# beltpack_v1.net
KiCad netlist of a schematic drawn in EAGLE
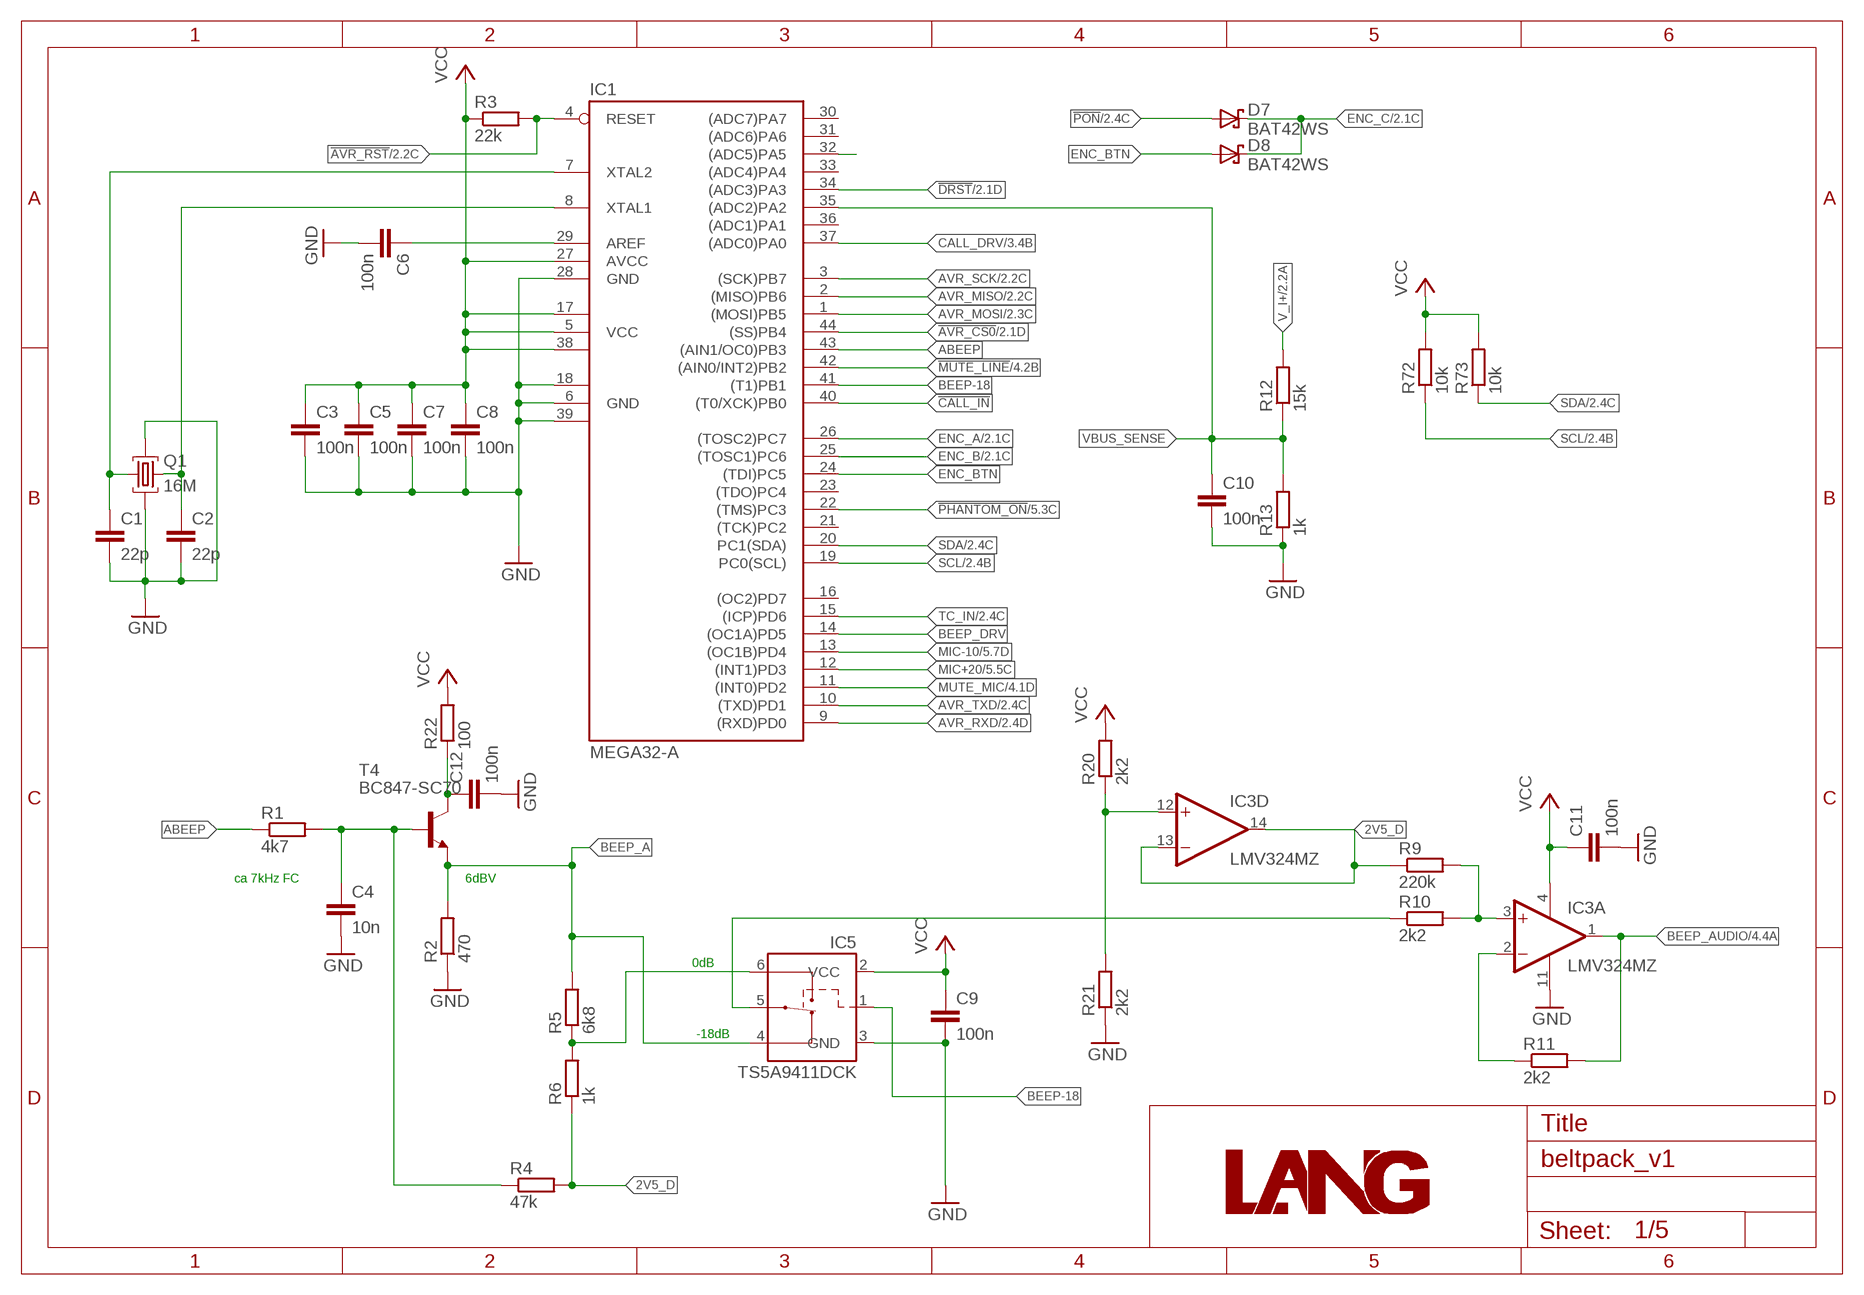
[diagram p0: schematic, sheet 1]
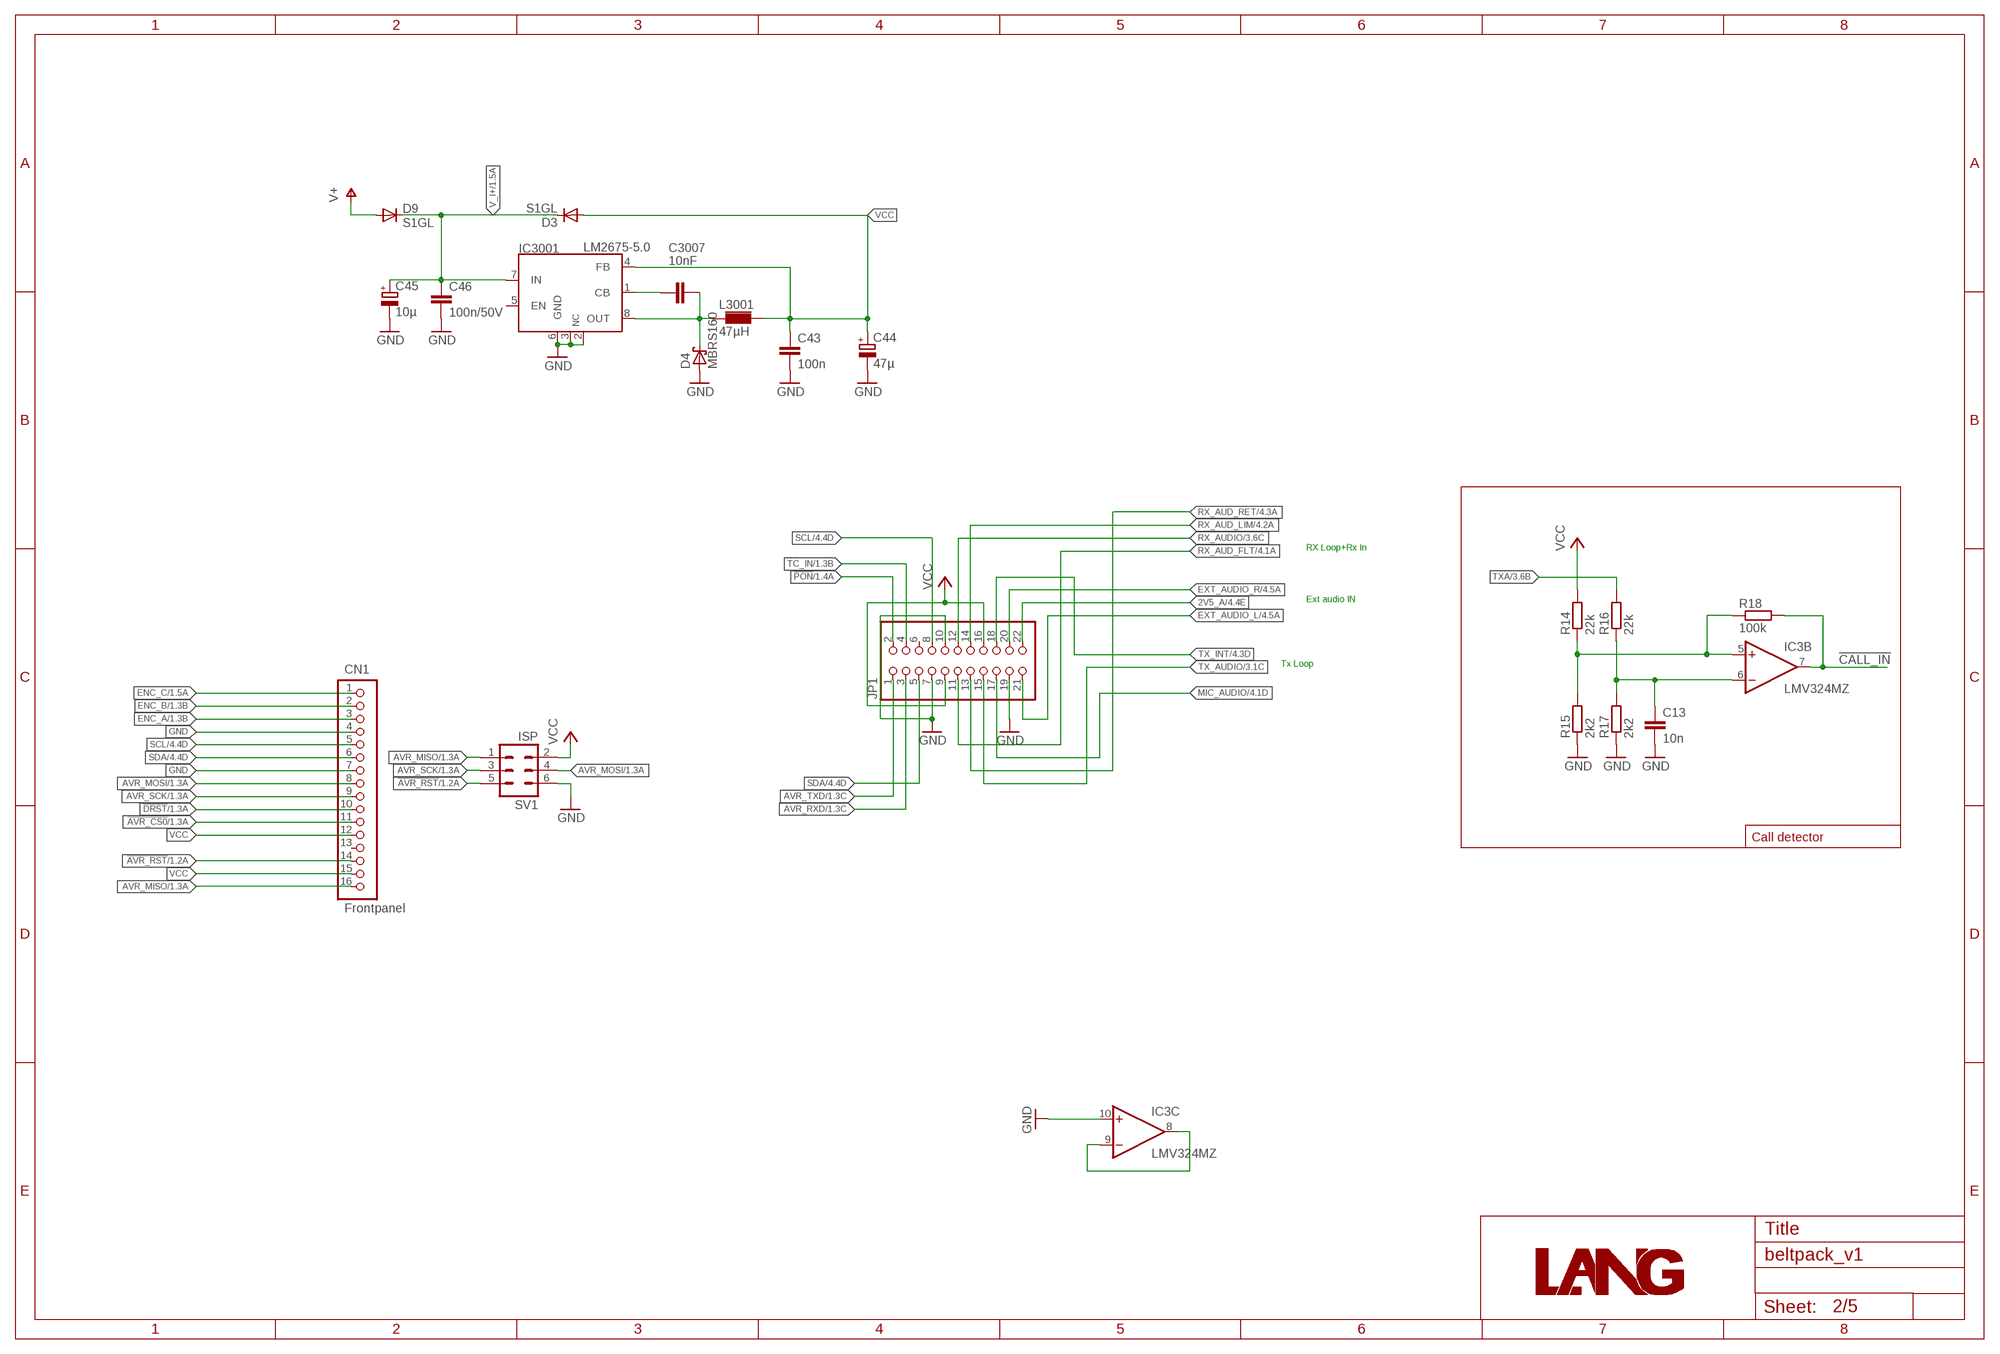
[diagram p1: schematic, sheet 2]
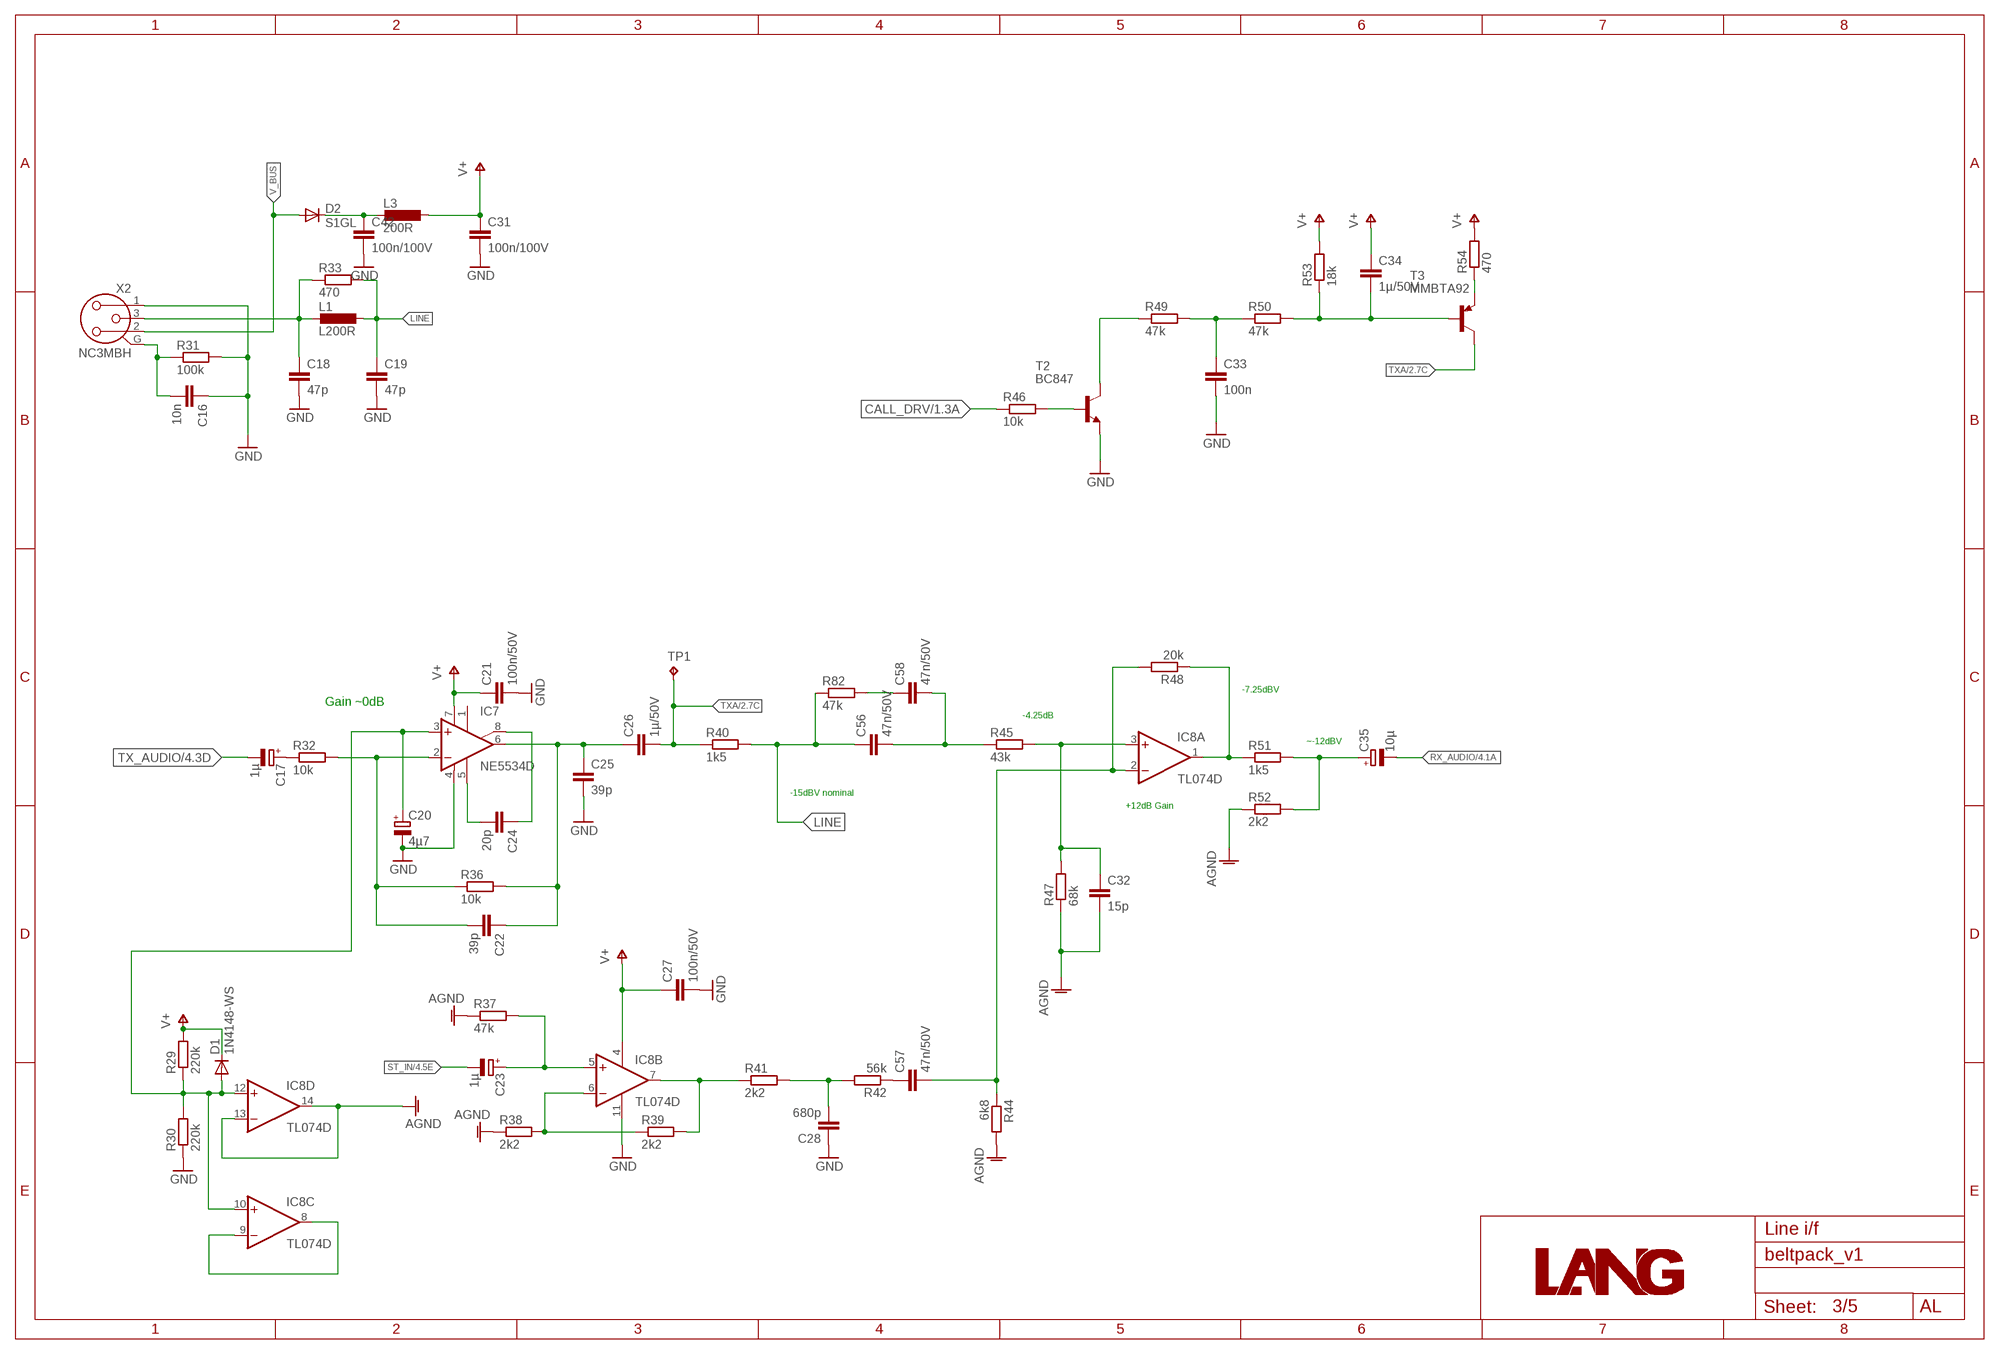
[diagram p2: schematic, sheet 3]
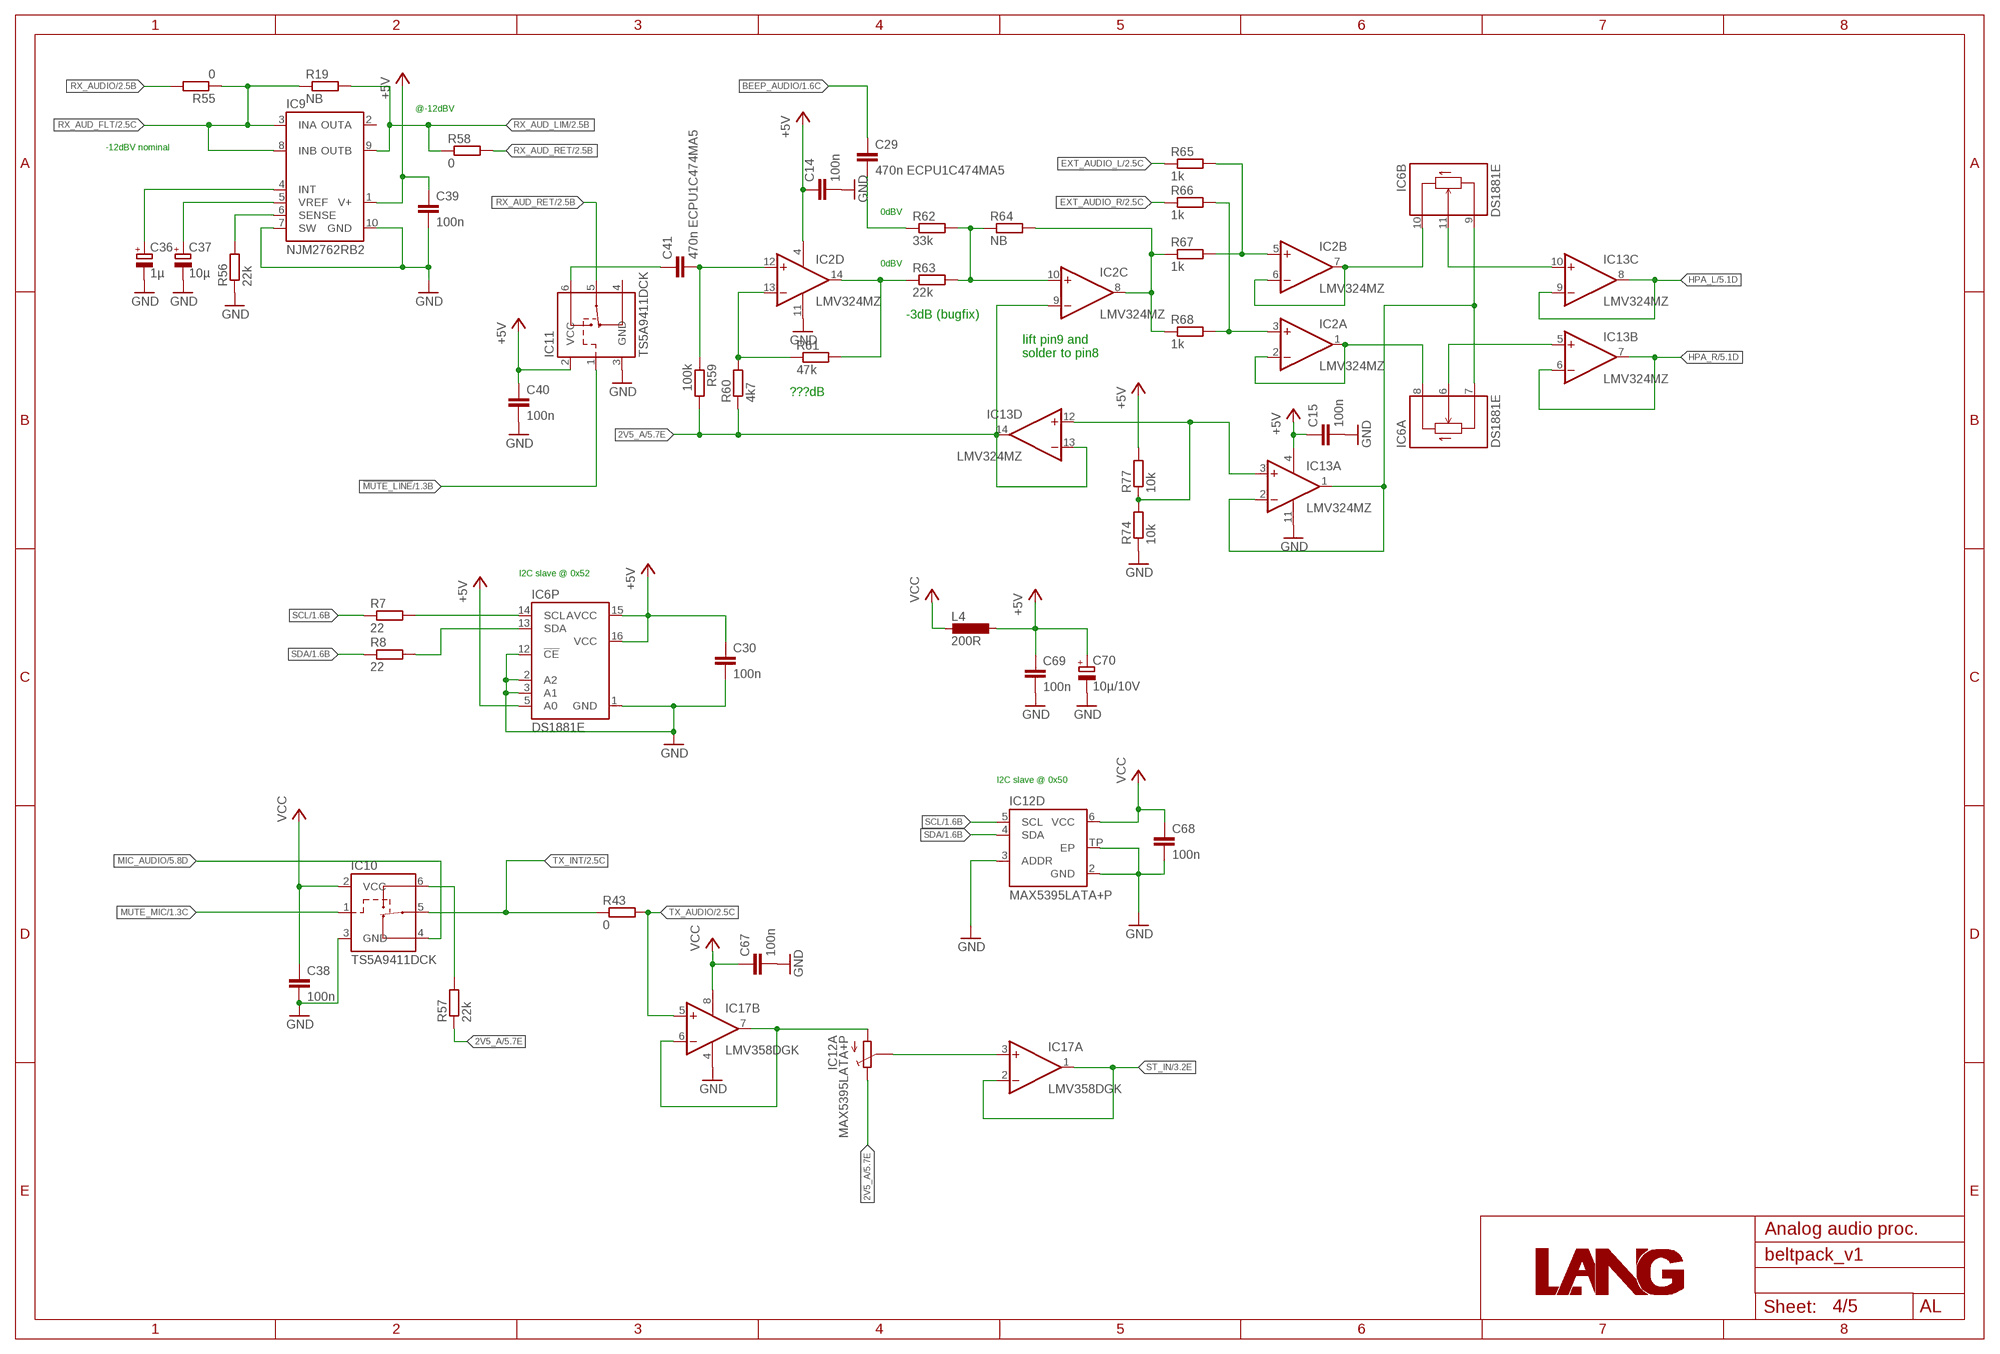
[diagram p3: schematic, sheet 4]
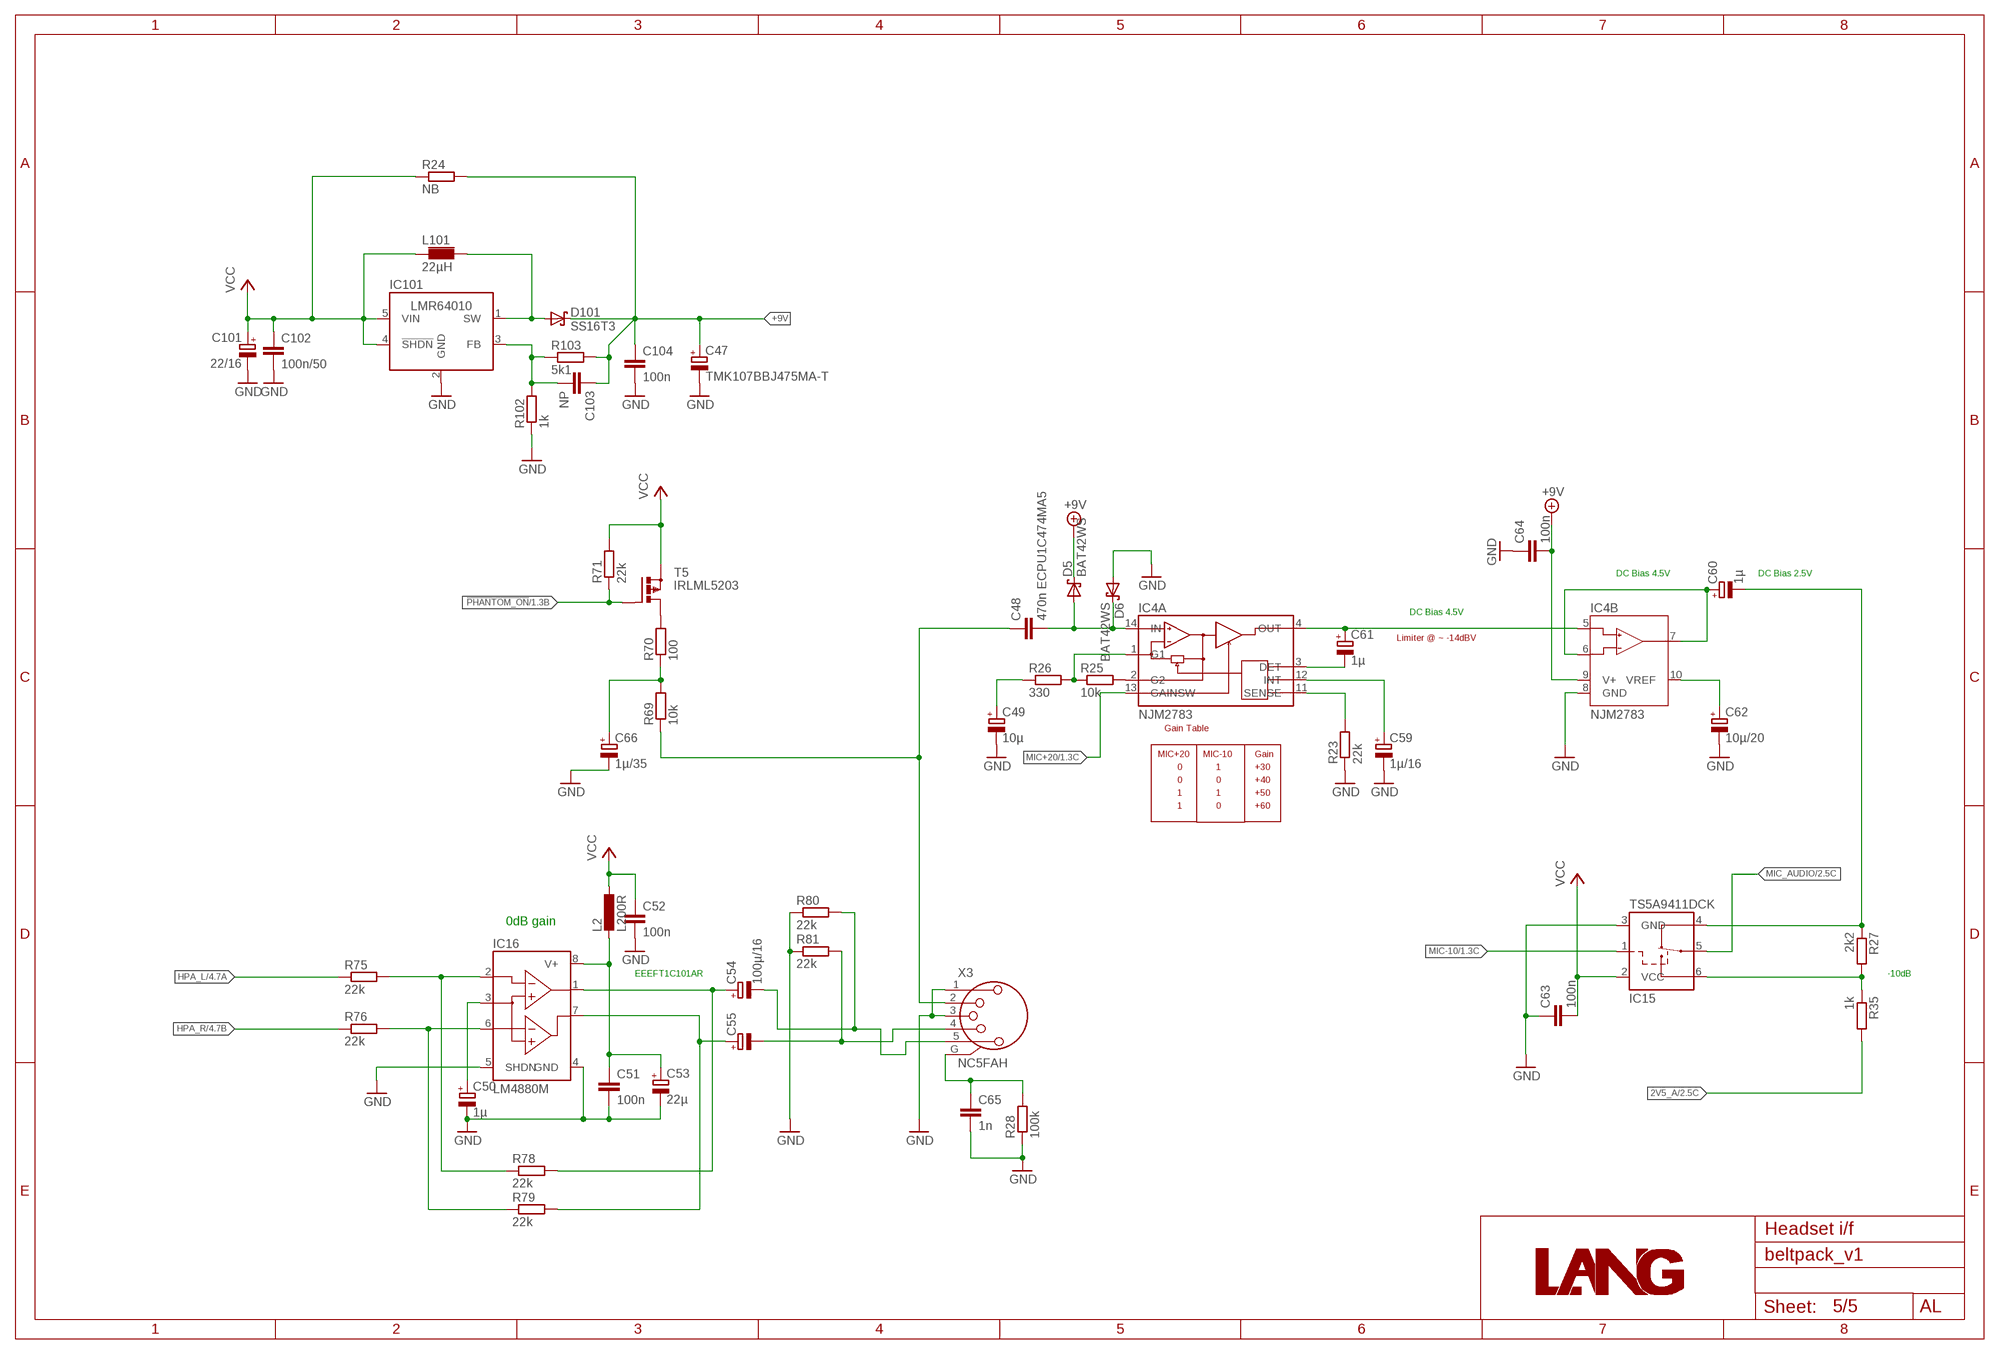
[diagram p4: schematic, sheet 5]

(export (version "E")
  (design (tool "Eeschema 10.0.6"))
  (components
    (comp (ref "C13")
      (value "10n")
      (footprint "eagle-import:C0603")
      (libsource (lib "eagle-import") (part "C-EUC0603"))
    )
    (comp (ref "C43")
      (value "100n")
      (footprint "eagle-import:C0603")
      (libsource (lib "eagle-import") (part "C-EUC0603"))
    )
    (comp (ref "C44")
      (value "47µ")
      (footprint "eagle-import:PANASONIC_B")
      (libsource (lib "eagle-import") (part "CPOL-EUB"))
    )
    (comp (ref "C45")
      (value "10µ")
      (footprint "eagle-import:PANASONIC_C")
      (libsource (lib "eagle-import") (part "CPOL-EUC"))
    )
    (comp (ref "C46")
      (value "100n/50V")
      (footprint "eagle-import:C0805")
      (libsource (lib "eagle-import") (part "C-EUC0805"))
    )
    (comp (ref "C3007")
      (value "10nF")
      (footprint "eagle-import:C0805")
      (libsource (lib "eagle-import") (part "C-EUC0805"))
    )
    (comp (ref "CN1")
      (value "Frontpanel")
      (footprint "eagle-import:MOLEX-505278-1633")
      (libsource (lib "eagle-import") (part "MOLEX-505278-1633"))
    )
    (comp (ref "D3")
      (value "S1GL")
      (footprint "eagle-import:DO219AB")
      (libsource (lib "eagle-import") (part "DIODE-DO219AB"))
    )
    (comp (ref "D4")
      (value "MBRS160")
      (footprint "eagle-import:SMB")
      (libsource (lib "eagle-import") (part "SCHOTTKY-DIODESMD"))
    )
    (comp (ref "D9")
      (value "S1GL")
      (footprint "eagle-import:DO219AB")
      (libsource (lib "eagle-import") (part "DIODE-DO219AB"))
    )
    (comp (ref "IC3")
      (value "LMV324MZ")
      (footprint "eagle-import:TSSOP14")
      (libsource (lib "eagle-import") (part "LMV324?MZ"))
    )
    (comp (ref "IC3001")
      (value "LM2675-5.0")
      (footprint "eagle-import:SO-08")
      (libsource (lib "eagle-import") (part "LM2676_SOIC"))
    )
    (comp (ref "JP1")
      (value "PINHD-2X11")
      (footprint "eagle-import:2X11")
      (libsource (lib "eagle-import") (part "PINHD-2X11"))
    )
    (comp (ref "L3001")
      (value "47µH")
      (footprint "eagle-import:PISM")
      (libsource (lib "eagle-import") (part "L-PISM"))
    )
    (comp (ref "R14")
      (value "22k")
      (footprint "eagle-import:R0603")
      (libsource (lib "eagle-import") (part "R-EU_R0603"))
    )
    (comp (ref "R15")
      (value "2k2")
      (footprint "eagle-import:R0603")
      (libsource (lib "eagle-import") (part "R-EU_R0603"))
    )
    (comp (ref "R16")
      (value "22k")
      (footprint "eagle-import:R0603")
      (libsource (lib "eagle-import") (part "R-EU_R0603"))
    )
    (comp (ref "R17")
      (value "2k2")
      (footprint "eagle-import:R0603")
      (libsource (lib "eagle-import") (part "R-EU_R0603"))
    )
    (comp (ref "R18")
      (value "100k")
      (footprint "eagle-import:R0603")
      (libsource (lib "eagle-import") (part "R-EU_R0603"))
    )
    (comp (ref "SV1")
      (value "ISP")
      (footprint "eagle-import:ML6")
      (libsource (lib "eagle-import") (part "ML6"))
    )
    (comp (ref "C1")
      (value "22p")
      (footprint "eagle-import:C0603")
      (libsource (lib "eagle-import") (part "C-EUC0603"))
    )
    (comp (ref "C2")
      (value "22p")
      (footprint "eagle-import:C0603")
      (libsource (lib "eagle-import") (part "C-EUC0603"))
    )
    (comp (ref "C3")
      (value "100n")
      (footprint "eagle-import:C0603")
      (libsource (lib "eagle-import") (part "C-EUC0603"))
    )
    (comp (ref "C4")
      (value "10n")
      (footprint "eagle-import:C0603")
      (libsource (lib "eagle-import") (part "C-EUC0603"))
    )
    (comp (ref "C5")
      (value "100n")
      (footprint "eagle-import:C0603")
      (libsource (lib "eagle-import") (part "C-EUC0603"))
    )
    (comp (ref "C6")
      (value "100n")
      (footprint "eagle-import:C0603")
      (libsource (lib "eagle-import") (part "C-EUC0603"))
    )
    (comp (ref "C7")
      (value "100n")
      (footprint "eagle-import:C0603")
      (libsource (lib "eagle-import") (part "C-EUC0603"))
    )
    (comp (ref "C8")
      (value "100n")
      (footprint "eagle-import:C0603")
      (libsource (lib "eagle-import") (part "C-EUC0603"))
    )
    (comp (ref "C9")
      (value "100n")
      (footprint "eagle-import:C0603")
      (libsource (lib "eagle-import") (part "C-EUC0603"))
    )
    (comp (ref "C10")
      (value "100n")
      (footprint "eagle-import:C0603")
      (libsource (lib "eagle-import") (part "C-EUC0603"))
    )
    (comp (ref "C11")
      (value "100n")
      (footprint "eagle-import:C0603")
      (libsource (lib "eagle-import") (part "C-EUC0603"))
    )
    (comp (ref "C12")
      (value "100n")
      (footprint "eagle-import:C0603")
      (libsource (lib "eagle-import") (part "C-EUC0603"))
    )
    (comp (ref "D7")
      (value "BAT42WS")
      (footprint "eagle-import:SOD323R_INFINEON")
      (libsource (lib "eagle-import") (part "BAT4WS2"))
    )
    (comp (ref "D8")
      (value "BAT42WS")
      (footprint "eagle-import:SOD323R_INFINEON")
      (libsource (lib "eagle-import") (part "BAT4WS2"))
    )
    (comp (ref "IC1")
      (value "MEGA32-A")
      (footprint "eagle-import:TQFP44")
      (libsource (lib "eagle-import") (part "MEGA32-A"))
    )
    (comp (ref "IC5")
      (value "TS5A9411DCK")
      (footprint "eagle-import:SC70-6L")
      (libsource (lib "eagle-import") (part "TS5A9411DCK"))
    )
    (comp (ref "Q1")
      (value "16M")
      (footprint "eagle-import:MT")
      (libsource (lib "eagle-import") (part "CRYSTAL_SHIELDEDMT"))
    )
    (comp (ref "R1")
      (value "4k7")
      (footprint "eagle-import:R0603")
      (libsource (lib "eagle-import") (part "R-EU_R0603"))
    )
    (comp (ref "R2")
      (value "470")
      (footprint "eagle-import:R0603")
      (libsource (lib "eagle-import") (part "R-EU_R0603"))
    )
    (comp (ref "R3")
      (value "22k")
      (footprint "eagle-import:R0603")
      (libsource (lib "eagle-import") (part "R-EU_R0603"))
    )
    (comp (ref "R4")
      (value "47k")
      (footprint "eagle-import:R0603")
      (libsource (lib "eagle-import") (part "R-EU_R0603"))
    )
    (comp (ref "R5")
      (value "6k8")
      (footprint "eagle-import:R0603")
      (libsource (lib "eagle-import") (part "R-EU_R0603"))
    )
    (comp (ref "R6")
      (value "1k")
      (footprint "eagle-import:R0603")
      (libsource (lib "eagle-import") (part "R-EU_R0603"))
    )
    (comp (ref "R9")
      (value "220k")
      (footprint "eagle-import:R0603")
      (libsource (lib "eagle-import") (part "R-EU_R0603"))
    )
    (comp (ref "R10")
      (value "2k2")
      (footprint "eagle-import:R0603")
      (libsource (lib "eagle-import") (part "R-EU_R0603"))
    )
    (comp (ref "R11")
      (value "2k2")
      (footprint "eagle-import:R0603")
      (libsource (lib "eagle-import") (part "R-EU_R0603"))
    )
    (comp (ref "R12")
      (value "15k")
      (footprint "eagle-import:R0603")
      (libsource (lib "eagle-import") (part "R-EU_R0603"))
    )
    (comp (ref "R13")
      (value "1k")
      (footprint "eagle-import:R0603")
      (libsource (lib "eagle-import") (part "R-EU_R0603"))
    )
    (comp (ref "R20")
      (value "2k2")
      (footprint "eagle-import:R0603")
      (libsource (lib "eagle-import") (part "R-EU_R0603"))
    )
    (comp (ref "R21")
      (value "2k2")
      (footprint "eagle-import:R0603")
      (libsource (lib "eagle-import") (part "R-EU_R0603"))
    )
    (comp (ref "R22")
      (value "100")
      (footprint "eagle-import:R0603")
      (libsource (lib "eagle-import") (part "R-EU_R0603"))
    )
    (comp (ref "R72")
      (value "10k")
      (footprint "eagle-import:R0603")
      (libsource (lib "eagle-import") (part "R-EU_R0603"))
    )
    (comp (ref "R73")
      (value "10k")
      (footprint "eagle-import:R0603")
      (libsource (lib "eagle-import") (part "R-EU_R0603"))
    )
    (comp (ref "T4")
      (value "BC847-SC70")
      (footprint "eagle-import:SC70")
      (libsource (lib "eagle-import") (part "BC847-SC70"))
    )
    (comp (ref "C16")
      (value "10n")
      (footprint "eagle-import:C0805")
      (libsource (lib "eagle-import") (part "C-EUC0805"))
    )
    (comp (ref "C17")
      (value "1µ")
      (footprint "eagle-import:PANASONIC_B")
      (libsource (lib "eagle-import") (part "CPOL-EUB"))
    )
    (comp (ref "C18")
      (value "47p")
      (footprint "eagle-import:C0603")
      (libsource (lib "eagle-import") (part "C-EUC0603"))
    )
    (comp (ref "C19")
      (value "47p")
      (footprint "eagle-import:C0603")
      (libsource (lib "eagle-import") (part "C-EUC0603"))
    )
    (comp (ref "C20")
      (value "4µ7")
      (footprint "eagle-import:PANASONIC_B")
      (libsource (lib "eagle-import") (part "CPOL-EUB"))
    )
    (comp (ref "C21")
      (value "100n/50V")
      (footprint "eagle-import:C0805")
      (libsource (lib "eagle-import") (part "C-EUC0805"))
    )
    (comp (ref "C22")
      (value "39p")
      (footprint "eagle-import:C0603")
      (libsource (lib "eagle-import") (part "C-EUC0603"))
    )
    (comp (ref "C23")
      (value "1µ")
      (footprint "eagle-import:PANASONIC_B")
      (libsource (lib "eagle-import") (part "CPOL-EUB"))
    )
    (comp (ref "C24")
      (value "20p")
      (footprint "eagle-import:C0603")
      (libsource (lib "eagle-import") (part "C-EUC0603"))
    )
    (comp (ref "C25")
      (value "39p")
      (footprint "eagle-import:C0603")
      (libsource (lib "eagle-import") (part "C-EUC0603"))
    )
    (comp (ref "C26")
      (value "1µ/50V")
      (footprint "eagle-import:C1206")
      (libsource (lib "eagle-import") (part "C-EUC1206"))
    )
    (comp (ref "C27")
      (value "100n/50V")
      (footprint "eagle-import:C0805")
      (libsource (lib "eagle-import") (part "C-EUC0805"))
    )
    (comp (ref "C28")
      (value "680p")
      (footprint "eagle-import:C0603")
      (libsource (lib "eagle-import") (part "C-EUC0603"))
    )
    (comp (ref "C31")
      (value "100n/100V")
      (footprint "eagle-import:C1206")
      (libsource (lib "eagle-import") (part "C-EUC1206"))
    )
    (comp (ref "C32")
      (value "15p")
      (footprint "eagle-import:C0603")
      (libsource (lib "eagle-import") (part "C-EUC0603"))
    )
    (comp (ref "C33")
      (value "100n")
      (footprint "eagle-import:C0603")
      (libsource (lib "eagle-import") (part "C-EUC0603"))
    )
    (comp (ref "C34")
      (value "1µ/50V")
      (footprint "eagle-import:C1206")
      (libsource (lib "eagle-import") (part "C-EUC1206"))
    )
    (comp (ref "C35")
      (value "10µ")
      (footprint "eagle-import:PANASONIC_B")
      (libsource (lib "eagle-import") (part "CPOL-EUB"))
    )
    (comp (ref "C42")
      (value "100n/100V")
      (footprint "eagle-import:C1206")
      (libsource (lib "eagle-import") (part "C-EUC1206"))
    )
    (comp (ref "C56")
      (value "47n/50V")
      (footprint "eagle-import:C_PAN_ECHU_E1")
      (libsource (lib "eagle-import") (part "C-EUPAN_E1"))
    )
    (comp (ref "C57")
      (value "47n/50V")
      (footprint "eagle-import:C_PAN_ECHU_E1")
      (libsource (lib "eagle-import") (part "C-EUPAN_E1"))
    )
    (comp (ref "C58")
      (value "47n/50V")
      (footprint "eagle-import:C_PAN_ECHU_E1")
      (libsource (lib "eagle-import") (part "C-EUPAN_E1"))
    )
    (comp (ref "D1")
      (value "1N4148-WS")
      (footprint "eagle-import:SOD323")
      (libsource (lib "eagle-import") (part "1N4148-WS"))
    )
    (comp (ref "D2")
      (value "S1GL")
      (footprint "eagle-import:DO219AB")
      (libsource (lib "eagle-import") (part "DIODE-DO219AB"))
    )
    (comp (ref "IC7")
      (value "NE5534D")
      (footprint "eagle-import:SO08")
      (libsource (lib "eagle-import") (part "NE5534D"))
    )
    (comp (ref "IC8")
      (value "TL074D")
      (footprint "eagle-import:SO14")
      (libsource (lib "eagle-import") (part "TL074D"))
    )
    (comp (ref "L1")
      (value "L200R")
      (footprint "eagle-import:R0805")
      (libsource (lib "eagle-import") (part "L-EU_L0805"))
    )
    (comp (ref "L3")
      (value "200R")
      (footprint "eagle-import:R0805")
      (libsource (lib "eagle-import") (part "L-EU_L0805"))
    )
    (comp (ref "R29")
      (value "220k")
      (footprint "eagle-import:R0603")
      (libsource (lib "eagle-import") (part "R-EU_R0603"))
    )
    (comp (ref "R30")
      (value "220k")
      (footprint "eagle-import:R0603")
      (libsource (lib "eagle-import") (part "R-EU_R0603"))
    )
    (comp (ref "R31")
      (value "100k")
      (footprint "eagle-import:R0805")
      (libsource (lib "eagle-import") (part "R-EU_R0805"))
    )
    (comp (ref "R32")
      (value "10k")
      (footprint "eagle-import:R0603")
      (libsource (lib "eagle-import") (part "R-EU_R0603"))
    )
    (comp (ref "R33")
      (value "470")
      (footprint "eagle-import:R0603")
      (libsource (lib "eagle-import") (part "R-EU_R0603"))
    )
    (comp (ref "R36")
      (value "10k")
      (footprint "eagle-import:R0603")
      (libsource (lib "eagle-import") (part "R-EU_R0603"))
    )
    (comp (ref "R37")
      (value "47k")
      (footprint "eagle-import:R0603")
      (libsource (lib "eagle-import") (part "R-EU_R0603"))
    )
    (comp (ref "R38")
      (value "2k2")
      (footprint "eagle-import:R0603")
      (libsource (lib "eagle-import") (part "R-EU_R0603"))
    )
    (comp (ref "R39")
      (value "2k2")
      (footprint "eagle-import:R0603")
      (libsource (lib "eagle-import") (part "R-EU_R0603"))
    )
    (comp (ref "R40")
      (value "1k5")
      (footprint "eagle-import:R1206")
      (libsource (lib "eagle-import") (part "R-EU_R1206"))
    )
    (comp (ref "R41")
      (value "2k2")
      (footprint "eagle-import:R0603")
      (libsource (lib "eagle-import") (part "R-EU_R0603"))
    )
    (comp (ref "R42")
      (value "56k")
      (footprint "eagle-import:R0603")
      (libsource (lib "eagle-import") (part "R-EU_R0603"))
    )
    (comp (ref "R44")
      (value "6k8")
      (footprint "eagle-import:R0603")
      (libsource (lib "eagle-import") (part "R-EU_R0603"))
    )
    (comp (ref "R45")
      (value "43k")
      (footprint "eagle-import:R0603")
      (libsource (lib "eagle-import") (part "R-EU_R0603"))
    )
    (comp (ref "R46")
      (value "10k")
      (footprint "eagle-import:R0603")
      (libsource (lib "eagle-import") (part "R-EU_R0603"))
    )
    (comp (ref "R47")
      (value "68k")
      (footprint "eagle-import:R0603")
      (libsource (lib "eagle-import") (part "R-EU_R0603"))
    )
    (comp (ref "R48")
      (value "20k")
      (footprint "eagle-import:R0603")
      (libsource (lib "eagle-import") (part "R-EU_R0603"))
    )
    (comp (ref "R49")
      (value "47k")
      (footprint "eagle-import:R0603")
      (libsource (lib "eagle-import") (part "R-EU_R0603"))
    )
    (comp (ref "R50")
      (value "47k")
      (footprint "eagle-import:R0603")
      (libsource (lib "eagle-import") (part "R-EU_R0603"))
    )
    (comp (ref "R51")
      (value "1k5")
      (footprint "eagle-import:R0603")
      (libsource (lib "eagle-import") (part "R-EU_R0603"))
    )
    (comp (ref "R52")
      (value "2k2")
      (footprint "eagle-import:R0603")
      (libsource (lib "eagle-import") (part "R-EU_R0603"))
    )
    (comp (ref "R53")
      (value "18k")
      (footprint "eagle-import:R0603")
      (libsource (lib "eagle-import") (part "R-EU_R0603"))
    )
    (comp (ref "R54")
      (value "470")
      (footprint "eagle-import:R0805")
      (libsource (lib "eagle-import") (part "R-EU_R0805"))
    )
    (comp (ref "R82")
      (value "47k")
      (footprint "eagle-import:R0603")
      (libsource (lib "eagle-import") (part "R-EU_R0603"))
    )
    (comp (ref "T2")
      (value "BC847")
      (footprint "eagle-import:SOT23")
      (libsource (lib "eagle-import") (part "BC847"))
    )
    (comp (ref "T3")
      (value "MMBTA92")
      (footprint "eagle-import:SOT23")
      (libsource (lib "eagle-import") (part "MMBTA92"))
    )
    (comp (ref "TP1")
      (value "XA")
      (footprint "eagle-import:B1,27")
      (libsource (lib "eagle-import") (part "TPB1,27"))
    )
    (comp (ref "X2")
      (value "NC3MBH")
      (footprint "eagle-import:NC3MBH")
      (libsource (lib "eagle-import") (part "NC3MBH"))
    )
    (comp (ref "C47")
      (value "TMK107BBJ475MA-T")
      (footprint "eagle-import:PANASONIC_B")
      (libsource (lib "eagle-import") (part "CPOL-EUB"))
    )
    (comp (ref "C48")
      (value "470n ECPU1C474MA5")
      (footprint "eagle-import:C_PANASONIC_H3")
      (libsource (lib "eagle-import") (part "C-EUPAN_H3"))
    )
    (comp (ref "C49")
      (value "10µ")
      (footprint "eagle-import:PANASONIC_B")
      (libsource (lib "eagle-import") (part "CPOL-EUB"))
    )
    (comp (ref "C50")
      (value "1µ")
      (footprint "eagle-import:PANASONIC_B")
      (libsource (lib "eagle-import") (part "CPOL-EUB"))
    )
    (comp (ref "C51")
      (value "100n")
      (footprint "eagle-import:C0603")
      (libsource (lib "eagle-import") (part "C-EUC0603"))
    )
    (comp (ref "C52")
      (value "100n")
      (footprint "eagle-import:C0603")
      (libsource (lib "eagle-import") (part "C-EUC0603"))
    )
    (comp (ref "C53")
      (value "22µ")
      (footprint "eagle-import:PANASONIC_C")
      (libsource (lib "eagle-import") (part "CPOL-EUC"))
    )
    (comp (ref "C54")
      (value "100µ/16")
      (footprint "eagle-import:PANASONIC_C")
      (libsource (lib "eagle-import") (part "CPOL-EUC"))
    )
    (comp (ref "C55")
      (value "100µ/16")
      (footprint "eagle-import:PANASONIC_C")
      (libsource (lib "eagle-import") (part "CPOL-EUC"))
    )
    (comp (ref "C59")
      (value "1µ/16")
      (footprint "eagle-import:A_3216-18R")
      (libsource (lib "eagle-import") (part "CPOL-EUA/3216-18R"))
    )
    (comp (ref "C60")
      (value "1µ")
      (footprint "eagle-import:PANASONIC_B")
      (libsource (lib "eagle-import") (part "CPOL-EUB"))
    )
    (comp (ref "C61")
      (value "1µ")
      (footprint "eagle-import:PANASONIC_B")
      (libsource (lib "eagle-import") (part "CPOL-EUB"))
    )
    (comp (ref "C62")
      (value "10µ/20")
      (footprint "eagle-import:B_3528-21R")
      (libsource (lib "eagle-import") (part "CPOL-EUB/3528-21R"))
    )
    (comp (ref "C63")
      (value "100n")
      (footprint "eagle-import:C0402")
      (libsource (lib "eagle-import") (part "C-EUC0402"))
    )
    (comp (ref "C64")
      (value "100n")
      (footprint "eagle-import:C0603")
      (libsource (lib "eagle-import") (part "C-EUC0603"))
    )
    (comp (ref "C65")
      (value "1n")
      (footprint "eagle-import:C0603")
      (libsource (lib "eagle-import") (part "C-EUC0603"))
    )
    (comp (ref "C66")
      (value "1µ/35")
      (footprint "eagle-import:B_3528-21R")
      (libsource (lib "eagle-import") (part "CPOL-EUB/3528-21R"))
    )
    (comp (ref "C101")
      (value "22/16")
      (footprint "eagle-import:B_3528-21R")
      (libsource (lib "eagle-import") (part "CPOL-EUB/3528-21R"))
    )
    (comp (ref "C102")
      (value "100n/50")
      (footprint "eagle-import:C0805")
      (libsource (lib "eagle-import") (part "C-EUC0805"))
    )
    (comp (ref "C103")
      (value "NP")
      (footprint "eagle-import:C0603")
      (libsource (lib "eagle-import") (part "C-EUC0603"))
    )
    (comp (ref "C104")
      (value "100n")
      (footprint "eagle-import:C0603")
      (libsource (lib "eagle-import") (part "C-EUC0603"))
    )
    (comp (ref "D5")
      (value "BAT42WS")
      (footprint "eagle-import:SOD323R_INFINEON")
      (libsource (lib "eagle-import") (part "BAT4WS2"))
    )
    (comp (ref "D6")
      (value "BAT42WS")
      (footprint "eagle-import:SOD323R_INFINEON")
      (libsource (lib "eagle-import") (part "BAT4WS2"))
    )
    (comp (ref "D101")
      (value "SS16T3")
      (footprint "eagle-import:SMA")
      (libsource (lib "eagle-import") (part "SS16T3"))
    )
    (comp (ref "IC4")
      (value "NJM2783")
      (footprint "eagle-import:TSSOP14")
      (libsource (lib "eagle-import") (part "NJM2783"))
    )
    (comp (ref "IC15")
      (value "TS5A9411DCK")
      (footprint "eagle-import:SC70-6L")
      (libsource (lib "eagle-import") (part "TS5A9411DCK"))
    )
    (comp (ref "IC16")
      (value "LM4880M")
      (footprint "eagle-import:SOIC8")
      (libsource (lib "eagle-import") (part "LM4880M"))
    )
    (comp (ref "IC101")
      (value "LMR64010")
      (footprint "eagle-import:SOT23-5")
      (libsource (lib "eagle-import") (part "LMR64010"))
    )
    (comp (ref "L2")
      (value "L200R")
      (footprint "eagle-import:R0805")
      (libsource (lib "eagle-import") (part "L-EU_L0805"))
    )
    (comp (ref "L101")
      (value "22µH")
      (footprint "eagle-import:PISG")
      (libsource (lib "eagle-import") (part "L-PISG"))
    )
    (comp (ref "R23")
      (value "22k")
      (footprint "eagle-import:R0603")
      (libsource (lib "eagle-import") (part "R-EU_R0603"))
    )
    (comp (ref "R24")
      (value "NB")
      (footprint "eagle-import:R0603")
      (libsource (lib "eagle-import") (part "R-EU_R0603"))
    )
    (comp (ref "R25")
      (value "10k")
      (footprint "eagle-import:R0603")
      (libsource (lib "eagle-import") (part "R-EU_R0603"))
    )
    (comp (ref "R26")
      (value "330")
      (footprint "eagle-import:R0603")
      (libsource (lib "eagle-import") (part "R-EU_R0603"))
    )
    (comp (ref "R27")
      (value "2k2")
      (footprint "eagle-import:R0603")
      (libsource (lib "eagle-import") (part "R-EU_R0603"))
    )
    (comp (ref "R28")
      (value "100k")
      (footprint "eagle-import:R0603")
      (libsource (lib "eagle-import") (part "R-EU_R0603"))
    )
    (comp (ref "R35")
      (value "1k")
      (footprint "eagle-import:R0603")
      (libsource (lib "eagle-import") (part "R-EU_R0603"))
    )
    (comp (ref "R69")
      (value "10k")
      (footprint "eagle-import:R0603")
      (libsource (lib "eagle-import") (part "R-EU_R0603"))
    )
    (comp (ref "R70")
      (value "100")
      (footprint "eagle-import:R0603")
      (libsource (lib "eagle-import") (part "R-EU_R0603"))
    )
    (comp (ref "R71")
      (value "22k")
      (footprint "eagle-import:R0603")
      (libsource (lib "eagle-import") (part "R-EU_R0603"))
    )
    (comp (ref "R75")
      (value "22k")
      (footprint "eagle-import:R0603")
      (libsource (lib "eagle-import") (part "R-EU_R0603"))
    )
    (comp (ref "R76")
      (value "22k")
      (footprint "eagle-import:R0603")
      (libsource (lib "eagle-import") (part "R-EU_R0603"))
    )
    (comp (ref "R78")
      (value "22k")
      (footprint "eagle-import:R0603")
      (libsource (lib "eagle-import") (part "R-EU_R0603"))
    )
    (comp (ref "R79")
      (value "22k")
      (footprint "eagle-import:R0603")
      (libsource (lib "eagle-import") (part "R-EU_R0603"))
    )
    (comp (ref "R80")
      (value "22k")
      (footprint "eagle-import:R0603")
      (libsource (lib "eagle-import") (part "R-EU_R0603"))
    )
    (comp (ref "R81")
      (value "22k")
      (footprint "eagle-import:R0603")
      (libsource (lib "eagle-import") (part "R-EU_R0603"))
    )
    (comp (ref "R102")
      (value "1k")
      (footprint "eagle-import:R0603")
      (libsource (lib "eagle-import") (part "R-EU_R0603"))
    )
    (comp (ref "R103")
      (value "5k1")
      (footprint "eagle-import:R0603")
      (libsource (lib "eagle-import") (part "R-EU_R0603"))
    )
    (comp (ref "T5")
      (value "IRLML5203")
      (footprint "eagle-import:SOT23")
      (libsource (lib "eagle-import") (part "IRLML5203"))
    )
    (comp (ref "X3")
      (value "NC5FAH")
      (footprint "eagle-import:NC5FAH")
      (libsource (lib "eagle-import") (part "NC5FAH"))
    )
    (comp (ref "C14")
      (value "100n")
      (footprint "eagle-import:C0603")
      (libsource (lib "eagle-import") (part "C-EUC0603"))
    )
    (comp (ref "C15")
      (value "100n")
      (footprint "eagle-import:C0603")
      (libsource (lib "eagle-import") (part "C-EUC0603"))
    )
    (comp (ref "C29")
      (value "470n ECPU1C474MA5")
      (footprint "eagle-import:C_PANASONIC_H3")
      (libsource (lib "eagle-import") (part "C-EUPAN_H3"))
    )
    (comp (ref "C30")
      (value "100n")
      (footprint "eagle-import:C0603")
      (libsource (lib "eagle-import") (part "C-EUC0603"))
    )
    (comp (ref "C36")
      (value "1µ")
      (footprint "eagle-import:PANASONIC_B")
      (libsource (lib "eagle-import") (part "CPOL-EUB"))
    )
    (comp (ref "C37")
      (value "10µ")
      (footprint "eagle-import:PANASONIC_B")
      (libsource (lib "eagle-import") (part "CPOL-EUB"))
    )
    (comp (ref "C38")
      (value "100n")
      (footprint "eagle-import:C0402")
      (libsource (lib "eagle-import") (part "C-EUC0402"))
    )
    (comp (ref "C39")
      (value "100n")
      (footprint "eagle-import:C0603")
      (libsource (lib "eagle-import") (part "C-EUC0603"))
    )
    (comp (ref "C40")
      (value "100n")
      (footprint "eagle-import:C0603")
      (libsource (lib "eagle-import") (part "C-EUC0603"))
    )
    (comp (ref "C41")
      (value "470n ECPU1C474MA5")
      (footprint "eagle-import:C_PANASONIC_H3")
      (libsource (lib "eagle-import") (part "C-EUPAN_H3"))
    )
    (comp (ref "C67")
      (value "100n")
      (footprint "eagle-import:C0603")
      (libsource (lib "eagle-import") (part "C-EUC0603"))
    )
    (comp (ref "C68")
      (value "100n")
      (footprint "eagle-import:C0603")
      (libsource (lib "eagle-import") (part "C-EUC0603"))
    )
    (comp (ref "C69")
      (value "100n")
      (footprint "eagle-import:C0603")
      (libsource (lib "eagle-import") (part "C-EUC0603"))
    )
    (comp (ref "C70")
      (value "10µ/10V")
      (footprint "eagle-import:A_3216-18R")
      (libsource (lib "eagle-import") (part "CPOL-EUA/3216-18R"))
    )
    (comp (ref "IC2")
      (value "LMV324MZ")
      (footprint "eagle-import:TSSOP14")
      (libsource (lib "eagle-import") (part "LMV324?MZ"))
    )
    (comp (ref "IC6")
      (value "DS1881E")
      (footprint "eagle-import:TSSOP16")
      (libsource (lib "eagle-import") (part "DS1881E"))
    )
    (comp (ref "IC9")
      (value "NJM2762RB2")
      (footprint "eagle-import:MSOP10")
      (libsource (lib "eagle-import") (part "NJM2762RB2"))
    )
    (comp (ref "IC10")
      (value "TS5A9411DCK")
      (footprint "eagle-import:SC70-6L")
      (libsource (lib "eagle-import") (part "TS5A9411DCK"))
    )
    (comp (ref "IC11")
      (value "TS5A9411DCK")
      (footprint "eagle-import:SC70-6L")
      (libsource (lib "eagle-import") (part "TS5A9411DCK"))
    )
    (comp (ref "IC12")
      (value "MAX5395LATA+P")
      (footprint "eagle-import:8TDFN-EP")
      (libsource (lib "eagle-import") (part "MAX5395ATA+PL"))
    )
    (comp (ref "IC13")
      (value "LMV324MZ")
      (footprint "eagle-import:TSSOP14")
      (libsource (lib "eagle-import") (part "LMV324?MZ"))
    )
    (comp (ref "IC17")
      (value "LMV358DGK")
      (footprint "eagle-import:VSOP8")
      (libsource (lib "eagle-import") (part "LMV358?DGK"))
    )
    (comp (ref "L4")
      (value "200R")
      (footprint "eagle-import:R0805")
      (libsource (lib "eagle-import") (part "L-EU_L0805"))
    )
    (comp (ref "R7")
      (value "22")
      (footprint "eagle-import:R0402")
      (libsource (lib "eagle-import") (part "R-EU_R0402"))
    )
    (comp (ref "R8")
      (value "22")
      (footprint "eagle-import:R0402")
      (libsource (lib "eagle-import") (part "R-EU_R0402"))
    )
    (comp (ref "R19")
      (value "NB")
      (footprint "eagle-import:R0603")
      (libsource (lib "eagle-import") (part "R-EU_R0603"))
    )
    (comp (ref "R43")
      (value "0")
      (footprint "eagle-import:R0603")
      (libsource (lib "eagle-import") (part "R-EU_R0603"))
    )
    (comp (ref "R55")
      (value "0")
      (footprint "eagle-import:R0603")
      (libsource (lib "eagle-import") (part "R-EU_R0603"))
    )
    (comp (ref "R56")
      (value "22k")
      (footprint "eagle-import:R0603")
      (libsource (lib "eagle-import") (part "R-EU_R0603"))
    )
    (comp (ref "R57")
      (value "22k")
      (footprint "eagle-import:R0603")
      (libsource (lib "eagle-import") (part "R-EU_R0603"))
    )
    (comp (ref "R58")
      (value "0")
      (footprint "eagle-import:R0603")
      (libsource (lib "eagle-import") (part "R-EU_R0603"))
    )
    (comp (ref "R59")
      (value "100k")
      (footprint "eagle-import:R0603")
      (libsource (lib "eagle-import") (part "R-EU_R0603"))
    )
    (comp (ref "R60")
      (value "4k7")
      (footprint "eagle-import:R0603")
      (libsource (lib "eagle-import") (part "R-EU_R0603"))
    )
    (comp (ref "R61")
      (value "47k")
      (footprint "eagle-import:R0603")
      (libsource (lib "eagle-import") (part "R-EU_R0603"))
    )
    (comp (ref "R62")
      (value "33k")
      (footprint "eagle-import:R0603")
      (libsource (lib "eagle-import") (part "R-EU_R0603"))
    )
    (comp (ref "R63")
      (value "22k")
      (footprint "eagle-import:R0603")
      (libsource (lib "eagle-import") (part "R-EU_R0603"))
    )
    (comp (ref "R64")
      (value "NB")
      (footprint "eagle-import:R0603")
      (libsource (lib "eagle-import") (part "R-EU_R0603"))
    )
    (comp (ref "R65")
      (value "1k")
      (footprint "eagle-import:R0603")
      (libsource (lib "eagle-import") (part "R-EU_R0603"))
    )
    (comp (ref "R66")
      (value "1k")
      (footprint "eagle-import:R0603")
      (libsource (lib "eagle-import") (part "R-EU_R0603"))
    )
    (comp (ref "R67")
      (value "1k")
      (footprint "eagle-import:R0603")
      (libsource (lib "eagle-import") (part "R-EU_R0603"))
    )
    (comp (ref "R68")
      (value "1k")
      (footprint "eagle-import:R0603")
      (libsource (lib "eagle-import") (part "R-EU_R0603"))
    )
    (comp (ref "R74")
      (value "10k")
      (footprint "eagle-import:R0603")
      (libsource (lib "eagle-import") (part "R-EU_R0603"))
    )
    (comp (ref "R77")
      (value "10k")
      (footprint "eagle-import:R0603")
      (libsource (lib "eagle-import") (part "R-EU_R0603"))
    )
  )
  (nets
    (net (code "1") (name "+5V") (class "Default")
      (node (ref "C14") (pin "1") (pinfunction "1_1") (pintype "passive"))
      (node (ref "C15") (pin "1") (pinfunction "1_1") (pintype "passive"))
      (node (ref "C30") (pin "1") (pinfunction "1_1") (pintype "passive"))
      (node (ref "C39") (pin "1") (pinfunction "1_1") (pintype "passive"))
      (node (ref "C40") (pin "1") (pinfunction "1_1") (pintype "passive"))
      (node (ref "C69") (pin "1") (pinfunction "1_1") (pintype "passive"))
      (node (ref "C70") (pin "+") (pinfunction "+_+") (pintype "passive"))
      (node (ref "IC11") (pin "2") (pinfunction "VCC_2") (pintype "power_in"))
      (node (ref "IC13") (pin "4") (pinfunction "V+_4") (pintype "power_in"))
      (node (ref "IC2") (pin "4") (pinfunction "V+_4") (pintype "power_in"))
      (node (ref "IC6") (pin "15") (pinfunction "AVCC_15") (pintype "power_in"))
      (node (ref "IC6") (pin "16") (pinfunction "VCC_16") (pintype "power_in"))
      (node (ref "IC6") (pin "5") (pinfunction "A0_5") (pintype "input"))
      (node (ref "IC9") (pin "1") (pinfunction "V+_1") (pintype "power_in"))
      (node (ref "L4") (pin "1") (pinfunction "1_1") (pintype "passive"))
      (node (ref "R77") (pin "2") (pinfunction "2_2") (pintype "passive"))
    )
    (net (code "2") (name "+9V") (class "Default")
      (node (ref "C103") (pin "1") (pinfunction "1_1") (pintype "passive"))
      (node (ref "C104") (pin "1") (pinfunction "1_1") (pintype "passive"))
      (node (ref "C47") (pin "+") (pinfunction "+_+") (pintype "passive"))
      (node (ref "C64") (pin "2") (pinfunction "2_2") (pintype "passive"))
      (node (ref "D101") (pin "C") (pinfunction "K_C") (pintype "bidirectional"))
      (node (ref "D5") (pin "C") (pinfunction "K_C") (pintype "bidirectional"))
      (node (ref "IC4") (pin "9") (pinfunction "V+_9") (pintype "power_in"))
      (node (ref "R103") (pin "2") (pinfunction "2_2") (pintype "passive"))
      (node (ref "R24") (pin "2") (pinfunction "2_2") (pintype "passive"))
    )
    (net (code "3") (name "2V5_A") (class "Default")
      (node (ref "IC12") (pin "8") (pinfunction "E_8") (pintype "passive"))
      (node (ref "IC13") (pin "13") (pinfunction "-IN_13") (pintype "input"))
      (node (ref "IC13") (pin "14") (pinfunction "OUT_14") (pintype "output"))
      (node (ref "IC2") (pin "9") (pinfunction "-IN_9") (pintype "input"))
      (node (ref "JP1") (pin "22") (pinfunction "22_22") (pintype "passive"))
      (node (ref "R35") (pin "2") (pinfunction "2_2") (pintype "passive"))
      (node (ref "R57") (pin "1") (pinfunction "1_1") (pintype "passive"))
      (node (ref "R59") (pin "2") (pinfunction "2_2") (pintype "passive"))
      (node (ref "R60") (pin "1") (pinfunction "1_1") (pintype "passive"))
    )
    (net (code "4") (name "2V5_D") (class "Default")
      (node (ref "IC3") (pin "13") (pinfunction "-IN_13") (pintype "input"))
      (node (ref "IC3") (pin "14") (pinfunction "OUT_14") (pintype "output"))
      (node (ref "R4") (pin "2") (pinfunction "2_2") (pintype "passive"))
      (node (ref "R6") (pin "1") (pinfunction "1_1") (pintype "passive"))
      (node (ref "R9") (pin "1") (pinfunction "1_1") (pintype "passive"))
    )
    (net (code "5") (name "ABEEP") (class "Default")
      (node (ref "IC1") (pin "43") (pinfunction "(AIN1/OC0)PB3_43") (pintype "bidirectional"))
      (node (ref "R1") (pin "1") (pinfunction "1_1") (pintype "passive"))
    )
    (net (code "6") (name "AGND") (class "Default")
      (node (ref "C32") (pin "2") (pinfunction "2_2") (pintype "passive"))
      (node (ref "IC8") (pin "13") (pinfunction "-IN_13") (pintype "input"))
      (node (ref "IC8") (pin "14") (pinfunction "OUT_14") (pintype "output"))
      (node (ref "R37") (pin "1") (pinfunction "1_1") (pintype "passive"))
      (node (ref "R38") (pin "1") (pinfunction "1_1") (pintype "passive"))
      (node (ref "R44") (pin "2") (pinfunction "2_2") (pintype "passive"))
      (node (ref "R47") (pin "1") (pinfunction "1_1") (pintype "passive"))
      (node (ref "R52") (pin "1") (pinfunction "1_1") (pintype "passive"))
    )
    (net (code "7") (name "AVR_MISO") (class "Default")
      (node (ref "CN1") (pin "16") (pinfunction "16_16") (pintype "bidirectional"))
      (node (ref "IC1") (pin "2") (pinfunction "(MISO)PB6_2") (pintype "bidirectional"))
      (node (ref "SV1") (pin "1") (pinfunction "1_1") (pintype "passive"))
    )
    (net (code "8") (name "AVR_MOSI") (class "Default")
      (node (ref "CN1") (pin "8") (pinfunction "8_8") (pintype "bidirectional"))
      (node (ref "IC1") (pin "1") (pinfunction "(MOSI)PB5_1") (pintype "bidirectional"))
      (node (ref "SV1") (pin "4") (pinfunction "4_4") (pintype "passive"))
    )
    (net (code "9") (name "AVR_RXD") (class "Default")
      (node (ref "IC1") (pin "9") (pinfunction "(RXD)PD0_9") (pintype "bidirectional"))
      (node (ref "JP1") (pin "3") (pinfunction "3_3") (pintype "passive"))
    )
    (net (code "10") (name "AVR_SCK") (class "Default")
      (node (ref "CN1") (pin "9") (pinfunction "9_9") (pintype "bidirectional"))
      (node (ref "IC1") (pin "3") (pinfunction "(SCK)PB7_3") (pintype "bidirectional"))
      (node (ref "SV1") (pin "3") (pinfunction "3_3") (pintype "passive"))
    )
    (net (code "11") (name "AVR_TXD") (class "Default")
      (node (ref "IC1") (pin "10") (pinfunction "(TXD)PD1_10") (pintype "bidirectional"))
      (node (ref "JP1") (pin "1") (pinfunction "1_1") (pintype "passive"))
    )
    (net (code "12") (name "BEEP-18") (class "Default")
      (node (ref "IC1") (pin "41") (pinfunction "(T1)PB1_41") (pintype "bidirectional"))
      (node (ref "IC5") (pin "1") (pinfunction "CTL_1") (pintype "input"))
    )
    (net (code "13") (name "BEEP_A") (class "Default")
      (node (ref "IC5") (pin "4") (pinfunction "NC_4") (pintype "passive"))
      (node (ref "R2") (pin "2") (pinfunction "2_2") (pintype "passive"))
      (node (ref "R5") (pin "2") (pinfunction "2_2") (pintype "passive"))
      (node (ref "T4") (pin "2") (pinfunction "E_2") (pintype "passive"))
    )
    (net (code "14") (name "BEEP_AUDIO") (class "Default")
      (node (ref "C29") (pin "1") (pinfunction "1_1") (pintype "passive"))
      (node (ref "IC3") (pin "1") (pinfunction "OUT_1") (pintype "output"))
      (node (ref "R11") (pin "2") (pinfunction "2_2") (pintype "passive"))
    )
    (net (code "15") (name "BEEP_DRV") (class "Default")
      (node (ref "IC1") (pin "14") (pinfunction "(OC1A)PD5_14") (pintype "bidirectional"))
    )
    (net (code "16") (name "CALL_DRV") (class "Default")
      (node (ref "IC1") (pin "37") (pinfunction "(ADC0)PA0_37") (pintype "bidirectional"))
      (node (ref "R46") (pin "1") (pinfunction "1_1") (pintype "passive"))
    )
    (net (code "17") (name "ENC_A") (class "Default")
      (node (ref "CN1") (pin "3") (pinfunction "3_3") (pintype "bidirectional"))
      (node (ref "IC1") (pin "26") (pinfunction "(TOSC2)PC7_26") (pintype "bidirectional"))
    )
    (net (code "18") (name "ENC_B") (class "Default")
      (node (ref "CN1") (pin "2") (pinfunction "2_2") (pintype "bidirectional"))
      (node (ref "IC1") (pin "25") (pinfunction "(TOSC1)PC6_25") (pintype "bidirectional"))
    )
    (net (code "19") (name "ENC_BTN") (class "Default")
      (node (ref "D8") (pin "A") (pinfunction "A_A") (pintype "bidirectional"))
      (node (ref "IC1") (pin "24") (pinfunction "(TDI)PC5_24") (pintype "bidirectional"))
    )
    (net (code "20") (name "ENC_C") (class "Default")
      (node (ref "CN1") (pin "1") (pinfunction "1_1") (pintype "bidirectional"))
      (node (ref "D7") (pin "C") (pinfunction "K_C") (pintype "bidirectional"))
      (node (ref "D8") (pin "C") (pinfunction "K_C") (pintype "bidirectional"))
    )
    (net (code "21") (name "EXT_AUDIO_L") (class "Default")
      (node (ref "JP1") (pin "21") (pinfunction "21_21") (pintype "passive"))
      (node (ref "R65") (pin "1") (pinfunction "1_1") (pintype "passive"))
    )
    (net (code "22") (name "EXT_AUDIO_R") (class "Default")
      (node (ref "JP1") (pin "20") (pinfunction "20_20") (pintype "passive"))
      (node (ref "R66") (pin "1") (pinfunction "1_1") (pintype "passive"))
    )
    (net (code "23") (name "GND") (class "Default")
      (node (ref "C1") (pin "2") (pinfunction "2_2") (pintype "passive"))
      (node (ref "C10") (pin "2") (pinfunction "2_2") (pintype "passive"))
      (node (ref "C101") (pin "-") (pinfunction "-_-") (pintype "passive"))
      (node (ref "C102") (pin "2") (pinfunction "2_2") (pintype "passive"))
      (node (ref "C104") (pin "2") (pinfunction "2_2") (pintype "passive"))
      (node (ref "C11") (pin "2") (pinfunction "2_2") (pintype "passive"))
      (node (ref "C12") (pin "2") (pinfunction "2_2") (pintype "passive"))
      (node (ref "C13") (pin "2") (pinfunction "2_2") (pintype "passive"))
      (node (ref "C14") (pin "2") (pinfunction "2_2") (pintype "passive"))
      (node (ref "C15") (pin "2") (pinfunction "2_2") (pintype "passive"))
      (node (ref "C16") (pin "1") (pinfunction "1_1") (pintype "passive"))
      (node (ref "C18") (pin "2") (pinfunction "2_2") (pintype "passive"))
      (node (ref "C19") (pin "2") (pinfunction "2_2") (pintype "passive"))
      (node (ref "C2") (pin "2") (pinfunction "2_2") (pintype "passive"))
      (node (ref "C20") (pin "-") (pinfunction "-_-") (pintype "passive"))
      (node (ref "C21") (pin "2") (pinfunction "2_2") (pintype "passive"))
      (node (ref "C25") (pin "2") (pinfunction "2_2") (pintype "passive"))
      (node (ref "C27") (pin "2") (pinfunction "2_2") (pintype "passive"))
      (node (ref "C28") (pin "1") (pinfunction "1_1") (pintype "passive"))
      (node (ref "C3") (pin "2") (pinfunction "2_2") (pintype "passive"))
      (node (ref "C30") (pin "2") (pinfunction "2_2") (pintype "passive"))
      (node (ref "C31") (pin "2") (pinfunction "2_2") (pintype "passive"))
      (node (ref "C33") (pin "2") (pinfunction "2_2") (pintype "passive"))
      (node (ref "C36") (pin "-") (pinfunction "-_-") (pintype "passive"))
      (node (ref "C37") (pin "-") (pinfunction "-_-") (pintype "passive"))
      (node (ref "C38") (pin "2") (pinfunction "2_2") (pintype "passive"))
      (node (ref "C39") (pin "2") (pinfunction "2_2") (pintype "passive"))
      (node (ref "C4") (pin "2") (pinfunction "2_2") (pintype "passive"))
      (node (ref "C40") (pin "2") (pinfunction "2_2") (pintype "passive"))
      (node (ref "C42") (pin "2") (pinfunction "2_2") (pintype "passive"))
      (node (ref "C43") (pin "2") (pinfunction "2_2") (pintype "passive"))
      (node (ref "C44") (pin "-") (pinfunction "-_-") (pintype "passive"))
      (node (ref "C45") (pin "-") (pinfunction "-_-") (pintype "passive"))
      (node (ref "C46") (pin "2") (pinfunction "2_2") (pintype "passive"))
      (node (ref "C47") (pin "-") (pinfunction "-_-") (pintype "passive"))
      (node (ref "C49") (pin "-") (pinfunction "-_-") (pintype "passive"))
      (node (ref "C5") (pin "2") (pinfunction "2_2") (pintype "passive"))
      (node (ref "C50") (pin "-") (pinfunction "-_-") (pintype "passive"))
      (node (ref "C51") (pin "2") (pinfunction "2_2") (pintype "passive"))
      (node (ref "C52") (pin "2") (pinfunction "2_2") (pintype "passive"))
      (node (ref "C53") (pin "-") (pinfunction "-_-") (pintype "passive"))
      (node (ref "C59") (pin "-") (pinfunction "-_-") (pintype "passive"))
      (node (ref "C6") (pin "2") (pinfunction "2_2") (pintype "passive"))
      (node (ref "C62") (pin "-") (pinfunction "-_-") (pintype "passive"))
      (node (ref "C63") (pin "1") (pinfunction "1_1") (pintype "passive"))
      (node (ref "C64") (pin "1") (pinfunction "1_1") (pintype "passive"))
      (node (ref "C65") (pin "2") (pinfunction "2_2") (pintype "passive"))
      (node (ref "C66") (pin "-") (pinfunction "-_-") (pintype "passive"))
      (node (ref "C67") (pin "2") (pinfunction "2_2") (pintype "passive"))
      (node (ref "C68") (pin "2") (pinfunction "2_2") (pintype "passive"))
      (node (ref "C69") (pin "2") (pinfunction "2_2") (pintype "passive"))
      (node (ref "C7") (pin "2") (pinfunction "2_2") (pintype "passive"))
      (node (ref "C70") (pin "-") (pinfunction "-_-") (pintype "passive"))
      (node (ref "C8") (pin "2") (pinfunction "2_2") (pintype "passive"))
      (node (ref "C9") (pin "2") (pinfunction "2_2") (pintype "passive"))
      (node (ref "CN1") (pin "4") (pinfunction "4_4") (pintype "bidirectional"))
      (node (ref "CN1") (pin "7") (pinfunction "7_7") (pintype "bidirectional"))
      (node (ref "D4") (pin "A") (pinfunction "A_A") (pintype "passive"))
      (node (ref "D6") (pin "A") (pinfunction "A_A") (pintype "bidirectional"))
      (node (ref "IC1") (pin "18") (pinfunction "GND1_18") (pintype "power_in"))
      (node (ref "IC1") (pin "28") (pinfunction "GND_28") (pintype "power_in"))
      (node (ref "IC1") (pin "39") (pinfunction "GND2_39") (pintype "power_in"))
      (node (ref "IC1") (pin "6") (pinfunction "GND_6") (pintype "power_in"))
      (node (ref "IC10") (pin "3") (pinfunction "GND_3") (pintype "power_in"))
      (node (ref "IC101") (pin "2") (pinfunction "GND_2") (pintype "power_in"))
      (node (ref "IC11") (pin "3") (pinfunction "GND_3") (pintype "power_in"))
      (node (ref "IC12") (pin "2") (pinfunction "GND_2") (pintype "power_in"))
      (node (ref "IC12") (pin "3") (pinfunction "ADDR_3") (pintype "input"))
      (node (ref "IC12") (pin "TP") (pinfunction "EP_TP") (pintype "passive"))
      (node (ref "IC13") (pin "11") (pinfunction "V-_11") (pintype "power_in"))
      (node (ref "IC15") (pin "3") (pinfunction "GND_3") (pintype "power_in"))
      (node (ref "IC16") (pin "4") (pinfunction "GND_4") (pintype "bidirectional"))
      (node (ref "IC16") (pin "5") (pinfunction "SHDN_5") (pintype "bidirectional"))
      (node (ref "IC17") (pin "4") (pinfunction "V-_4") (pintype "power_in"))
      (node (ref "IC2") (pin "11") (pinfunction "V-_11") (pintype "power_in"))
      (node (ref "IC3") (pin "10") (pinfunction "+IN_10") (pintype "input"))
      (node (ref "IC3") (pin "11") (pinfunction "V-_11") (pintype "power_in"))
      (node (ref "IC3001") (pin "2") (pinfunction "NC_2") (pintype "bidirectional"))
      (node (ref "IC3001") (pin "3") (pinfunction "NC_3") (pintype "bidirectional"))
      (node (ref "IC3001") (pin "6") (pinfunction "GND_6") (pintype "bidirectional"))
      (node (ref "IC4") (pin "8") (pinfunction "GND_8") (pintype "power_in"))
      (node (ref "IC5") (pin "3") (pinfunction "GND_3") (pintype "power_in"))
      (node (ref "IC6") (pin "1") (pinfunction "GND_1") (pintype "power_in"))
      (node (ref "IC6") (pin "12") (pinfunction "~{CE}_12") (pintype "input"))
      (node (ref "IC6") (pin "2") (pinfunction "A2_2") (pintype "input"))
      (node (ref "IC6") (pin "3") (pinfunction "A1_3") (pintype "input"))
      (node (ref "IC7") (pin "4") (pinfunction "V-_4") (pintype "power_in"))
      (node (ref "IC8") (pin "11") (pinfunction "V-_11") (pintype "power_in"))
      (node (ref "IC9") (pin "10") (pinfunction "GND_10") (pintype "power_in"))
      (node (ref "IC9") (pin "7") (pinfunction "SW_7") (pintype "input"))
      (node (ref "JP1") (pin "10") (pinfunction "10_10") (pintype "passive"))
      (node (ref "JP1") (pin "19") (pinfunction "19_19") (pintype "passive"))
      (node (ref "JP1") (pin "7") (pinfunction "7_7") (pintype "passive"))
      (node (ref "Q1") (pin "2") (pinfunction "G1_2") (pintype "passive"))
      (node (ref "Q1") (pin "4") (pinfunction "G2_4") (pintype "passive"))
      (node (ref "R102") (pin "1") (pinfunction "1_1") (pintype "passive"))
      (node (ref "R13") (pin "1") (pinfunction "1_1") (pintype "passive"))
      (node (ref "R15") (pin "1") (pinfunction "1_1") (pintype "passive"))
      (node (ref "R17") (pin "1") (pinfunction "1_1") (pintype "passive"))
      (node (ref "R2") (pin "1") (pinfunction "1_1") (pintype "passive"))
      (node (ref "R21") (pin "1") (pinfunction "1_1") (pintype "passive"))
      (node (ref "R23") (pin "1") (pinfunction "1_1") (pintype "passive"))
      (node (ref "R28") (pin "1") (pinfunction "1_1") (pintype "passive"))
      (node (ref "R30") (pin "1") (pinfunction "1_1") (pintype "passive"))
      (node (ref "R31") (pin "2") (pinfunction "2_2") (pintype "passive"))
      (node (ref "R56") (pin "1") (pinfunction "1_1") (pintype "passive"))
      (node (ref "R74") (pin "1") (pinfunction "1_1") (pintype "passive"))
      (node (ref "R80") (pin "1") (pinfunction "1_1") (pintype "passive"))
      (node (ref "R81") (pin "1") (pinfunction "1_1") (pintype "passive"))
      (node (ref "SV1") (pin "6") (pinfunction "6_6") (pintype "passive"))
      (node (ref "T2") (pin "2") (pinfunction "E_2") (pintype "passive"))
      (node (ref "X2") (pin "1") (pinfunction "1_1") (pintype "passive"))
      (node (ref "X3") (pin "1") (pinfunction "1_1") (pintype "passive"))
      (node (ref "X3") (pin "3") (pinfunction "3_3") (pintype "passive"))
    )
    (net (code "24") (name "HPA_L") (class "Default")
      (node (ref "IC13") (pin "8") (pinfunction "OUT_8") (pintype "output"))
      (node (ref "IC13") (pin "9") (pinfunction "-IN_9") (pintype "input"))
      (node (ref "R75") (pin "1") (pinfunction "1_1") (pintype "passive"))
    )
    (net (code "25") (name "HPA_R") (class "Default")
      (node (ref "IC13") (pin "6") (pinfunction "-IN_6") (pintype "input"))
      (node (ref "IC13") (pin "7") (pinfunction "OUT_7") (pintype "output"))
      (node (ref "R76") (pin "1") (pinfunction "1_1") (pintype "passive"))
    )
    (net (code "26") (name "LINE") (class "Default")
      (node (ref "C19") (pin "1") (pinfunction "1_1") (pintype "passive"))
      (node (ref "C56") (pin "1") (pinfunction "1_1") (pintype "passive"))
      (node (ref "L1") (pin "1") (pinfunction "1_1") (pintype "passive"))
      (node (ref "R33") (pin "2") (pinfunction "2_2") (pintype "passive"))
      (node (ref "R40") (pin "2") (pinfunction "2_2") (pintype "passive"))
      (node (ref "R82") (pin "1") (pinfunction "1_1") (pintype "passive"))
    )
    (net (code "27") (name "MIC+20") (class "Default")
      (node (ref "IC1") (pin "12") (pinfunction "(INT1)PD3_12") (pintype "bidirectional"))
      (node (ref "IC4") (pin "13") (pinfunction "GAINSW_13") (pintype "input"))
    )
    (net (code "28") (name "MIC-10") (class "Default")
      (node (ref "IC1") (pin "13") (pinfunction "(OC1B)PD4_13") (pintype "bidirectional"))
      (node (ref "IC15") (pin "1") (pinfunction "CTL_1") (pintype "input"))
    )
    (net (code "29") (name "MIC_AUDIO") (class "Default")
      (node (ref "IC10") (pin "4") (pinfunction "NC_4") (pintype "passive"))
      (node (ref "IC15") (pin "5") (pinfunction "COM_5") (pintype "passive"))
      (node (ref "JP1") (pin "17") (pinfunction "17_17") (pintype "passive"))
    )
    (net (code "30") (name "MUTE_MIC") (class "Default")
      (node (ref "IC1") (pin "11") (pinfunction "(INT0)PD2_11") (pintype "bidirectional"))
      (node (ref "IC10") (pin "1") (pinfunction "CTL_1") (pintype "input"))
    )
    (net (code "31") (name "Net-(C16-Pad2)") (class "Default")
      (node (ref "C16") (pin "2") (pinfunction "2_2") (pintype "passive"))
      (node (ref "R31") (pin "1") (pinfunction "1_1") (pintype "passive"))
      (node (ref "X2") (pin "G") (pinfunction "G_G") (pintype "passive"))
    )
    (net (code "32") (name "Net-(C17-Pad+)") (class "Default")
      (node (ref "C17") (pin "+") (pinfunction "+_+") (pintype "passive"))
      (node (ref "R32") (pin "1") (pinfunction "1_1") (pintype "passive"))
    )
    (net (code "33") (name "Net-(C18-Pad1)") (class "Default")
      (node (ref "C18") (pin "1") (pinfunction "1_1") (pintype "passive"))
      (node (ref "L1") (pin "2") (pinfunction "2_2") (pintype "passive"))
      (node (ref "R33") (pin "1") (pinfunction "1_1") (pintype "passive"))
      (node (ref "X2") (pin "3") (pinfunction "3_3") (pintype "passive"))
    )
    (net (code "34") (name "Net-(C28-Pad2)") (class "Default")
      (node (ref "C28") (pin "2") (pinfunction "2_2") (pintype "passive"))
      (node (ref "R41") (pin "2") (pinfunction "2_2") (pintype "passive"))
      (node (ref "R42") (pin "2") (pinfunction "2_2") (pintype "passive"))
    )
    (net (code "35") (name "Net-(C29-Pad2)") (class "Default")
      (node (ref "C29") (pin "2") (pinfunction "2_2") (pintype "passive"))
      (node (ref "R62") (pin "1") (pinfunction "1_1") (pintype "passive"))
    )
    (net (code "36") (name "Net-(C33-Pad1)") (class "Default")
      (node (ref "C33") (pin "1") (pinfunction "1_1") (pintype "passive"))
      (node (ref "R49") (pin "2") (pinfunction "2_2") (pintype "passive"))
      (node (ref "R50") (pin "1") (pinfunction "1_1") (pintype "passive"))
    )
    (net (code "37") (name "Net-(C35-Pad+)") (class "Default")
      (node (ref "C35") (pin "+") (pinfunction "+_+") (pintype "passive"))
      (node (ref "R51") (pin "2") (pinfunction "2_2") (pintype "passive"))
      (node (ref "R52") (pin "2") (pinfunction "2_2") (pintype "passive"))
    )
    (net (code "38") (name "Net-(C42-Pad1)") (class "Default")
      (node (ref "C42") (pin "1") (pinfunction "1_1") (pintype "passive"))
      (node (ref "D2") (pin "C") (pinfunction "C_C") (pintype "passive"))
      (node (ref "L3") (pin "2") (pinfunction "2_2") (pintype "passive"))
    )
    (net (code "39") (name "Net-(C48-Pad1)") (class "Default")
      (node (ref "C48") (pin "1") (pinfunction "1_1") (pintype "passive"))
      (node (ref "R69") (pin "1") (pinfunction "1_1") (pintype "passive"))
      (node (ref "X3") (pin "2") (pinfunction "2_2") (pintype "passive"))
    )
    (net (code "40") (name "Net-(C49-Pad+)") (class "Default")
      (node (ref "C49") (pin "+") (pinfunction "+_+") (pintype "passive"))
      (node (ref "R26") (pin "1") (pinfunction "1_1") (pintype "passive"))
    )
    (net (code "41") (name "Net-(C54-Pad-)") (class "Default")
      (node (ref "C54") (pin "-") (pinfunction "-_-") (pintype "passive"))
      (node (ref "R80") (pin "2") (pinfunction "2_2") (pintype "passive"))
      (node (ref "X3") (pin "5") (pinfunction "5_5") (pintype "passive"))
    )
    (net (code "42") (name "Net-(C55-Pad-)") (class "Default")
      (node (ref "C55") (pin "-") (pinfunction "-_-") (pintype "passive"))
      (node (ref "R81") (pin "2") (pinfunction "2_2") (pintype "passive"))
      (node (ref "X3") (pin "4") (pinfunction "4_4") (pintype "passive"))
    )
    (net (code "43") (name "Net-(C56-Pad2)") (class "Default")
      (node (ref "C56") (pin "2") (pinfunction "2_2") (pintype "passive"))
      (node (ref "C58") (pin "2") (pinfunction "2_2") (pintype "passive"))
      (node (ref "R45") (pin "1") (pinfunction "1_1") (pintype "passive"))
    )
    (net (code "44") (name "Net-(C57-Pad1)") (class "Default")
      (node (ref "C57") (pin "1") (pinfunction "1_1") (pintype "passive"))
      (node (ref "R42") (pin "1") (pinfunction "1_1") (pintype "passive"))
    )
    (net (code "45") (name "Net-(C58-Pad1)") (class "Default")
      (node (ref "C58") (pin "1") (pinfunction "1_1") (pintype "passive"))
      (node (ref "R82") (pin "2") (pinfunction "2_2") (pintype "passive"))
    )
    (net (code "46") (name "Net-(C65-Pad1)") (class "Default")
      (node (ref "C65") (pin "1") (pinfunction "1_1") (pintype "passive"))
      (node (ref "R28") (pin "2") (pinfunction "2_2") (pintype "passive"))
      (node (ref "X3") (pin "G") (pinfunction "G_G") (pintype "passive"))
    )
    (net (code "47") (name "Net-(C66-Pad+)") (class "Default")
      (node (ref "C66") (pin "+") (pinfunction "+_+") (pintype "passive"))
      (node (ref "R69") (pin "2") (pinfunction "2_2") (pintype "passive"))
      (node (ref "R70") (pin "1") (pinfunction "1_1") (pintype "passive"))
    )
    (net (code "48") (name "Net-(D6-K)") (class "Default")
      (node (ref "C48") (pin "2") (pinfunction "2_2") (pintype "passive"))
      (node (ref "D5") (pin "A") (pinfunction "A_A") (pintype "bidirectional"))
      (node (ref "D6") (pin "C") (pinfunction "K_C") (pintype "bidirectional"))
      (node (ref "IC4") (pin "14") (pinfunction "IN_14") (pintype "input"))
    )
    (net (code "49") (name "Net-(IC1-AREF)") (class "Default")
      (node (ref "C6") (pin "1") (pinfunction "1_1") (pintype "passive"))
      (node (ref "IC1") (pin "29") (pinfunction "AREF_29") (pintype "passive"))
    )
    (net (code "50") (name "Net-(IC1-XTAL1)") (class "Default")
      (node (ref "C2") (pin "1") (pinfunction "1_1") (pintype "passive"))
      (node (ref "IC1") (pin "8") (pinfunction "XTAL1_8") (pintype "bidirectional"))
      (node (ref "Q1") (pin "3") (pinfunction "2_3") (pintype "passive"))
    )
    (net (code "51") (name "Net-(IC1-XTAL2)") (class "Default")
      (node (ref "C1") (pin "1") (pinfunction "1_1") (pintype "passive"))
      (node (ref "IC1") (pin "7") (pinfunction "XTAL2_7") (pintype "bidirectional"))
      (node (ref "Q1") (pin "1") (pinfunction "1_1") (pintype "passive"))
    )
    (net (code "52") (name "Net-(IC2A-+IN)") (class "Default")
      (node (ref "IC2") (pin "3") (pinfunction "+IN_3") (pintype "input"))
      (node (ref "R66") (pin "2") (pinfunction "2_2") (pintype "passive"))
      (node (ref "R68") (pin "2") (pinfunction "2_2") (pintype "passive"))
    )
    (net (code "53") (name "Net-(IC2A--IN)") (class "Default")
      (node (ref "IC2") (pin "1") (pinfunction "OUT_1") (pintype "output"))
      (node (ref "IC2") (pin "2") (pinfunction "-IN_2") (pintype "input"))
      (node (ref "IC6") (pin "8") (pinfunction "H_8") (pintype "passive"))
    )
    (net (code "54") (name "Net-(IC2B-+IN)") (class "Default")
      (node (ref "IC2") (pin "5") (pinfunction "+IN_5") (pintype "input"))
      (node (ref "R65") (pin "2") (pinfunction "2_2") (pintype "passive"))
      (node (ref "R67") (pin "2") (pinfunction "2_2") (pintype "passive"))
    )
    (net (code "55") (name "Net-(IC2B--IN)") (class "Default")
      (node (ref "IC2") (pin "6") (pinfunction "-IN_6") (pintype "input"))
      (node (ref "IC2") (pin "7") (pinfunction "OUT_7") (pintype "output"))
      (node (ref "IC6") (pin "10") (pinfunction "H_10") (pintype "passive"))
    )
    (net (code "56") (name "Net-(IC2C-+IN)") (class "Default")
      (node (ref "IC2") (pin "10") (pinfunction "+IN_10") (pintype "input"))
      (node (ref "R62") (pin "2") (pinfunction "2_2") (pintype "passive"))
      (node (ref "R63") (pin "2") (pinfunction "2_2") (pintype "passive"))
      (node (ref "R64") (pin "1") (pinfunction "1_1") (pintype "passive"))
    )
    (net (code "57") (name "Net-(IC2C-OUT)") (class "Default")
      (node (ref "IC2") (pin "8") (pinfunction "OUT_8") (pintype "output"))
      (node (ref "R64") (pin "2") (pinfunction "2_2") (pintype "passive"))
      (node (ref "R67") (pin "1") (pinfunction "1_1") (pintype "passive"))
      (node (ref "R68") (pin "1") (pinfunction "1_1") (pintype "passive"))
    )
    (net (code "58") (name "Net-(IC2D-+IN)") (class "Default")
      (node (ref "C41") (pin "2") (pinfunction "2_2") (pintype "passive"))
      (node (ref "IC2") (pin "12") (pinfunction "+IN_12") (pintype "input"))
      (node (ref "R59") (pin "1") (pinfunction "1_1") (pintype "passive"))
    )
    (net (code "59") (name "Net-(IC2D--IN)") (class "Default")
      (node (ref "IC2") (pin "13") (pinfunction "-IN_13") (pintype "input"))
      (node (ref "R60") (pin "2") (pinfunction "2_2") (pintype "passive"))
      (node (ref "R61") (pin "1") (pinfunction "1_1") (pintype "passive"))
    )
    (net (code "60") (name "Net-(IC2D-OUT)") (class "Default")
      (node (ref "IC2") (pin "14") (pinfunction "OUT_14") (pintype "output"))
      (node (ref "R61") (pin "2") (pinfunction "2_2") (pintype "passive"))
      (node (ref "R63") (pin "1") (pinfunction "1_1") (pintype "passive"))
    )
    (net (code "61") (name "Net-(IC3A-+IN)") (class "Default")
      (node (ref "IC3") (pin "3") (pinfunction "+IN_3") (pintype "input"))
      (node (ref "R10") (pin "2") (pinfunction "2_2") (pintype "passive"))
      (node (ref "R9") (pin "2") (pinfunction "2_2") (pintype "passive"))
    )
    (net (code "62") (name "Net-(IC3A--IN)") (class "Default")
      (node (ref "IC3") (pin "2") (pinfunction "-IN_2") (pintype "input"))
      (node (ref "R11") (pin "1") (pinfunction "1_1") (pintype "passive"))
    )
    (net (code "63") (name "Net-(IC3B-+IN)") (class "Default")
      (node (ref "IC3") (pin "5") (pinfunction "+IN_5") (pintype "input"))
      (node (ref "R14") (pin "1") (pinfunction "1_1") (pintype "passive"))
      (node (ref "R15") (pin "2") (pinfunction "2_2") (pintype "passive"))
      (node (ref "R18") (pin "1") (pinfunction "1_1") (pintype "passive"))
    )
    (net (code "64") (name "Net-(IC3B--IN)") (class "Default")
      (node (ref "C13") (pin "1") (pinfunction "1_1") (pintype "passive"))
      (node (ref "IC3") (pin "6") (pinfunction "-IN_6") (pintype "input"))
      (node (ref "R16") (pin "1") (pinfunction "1_1") (pintype "passive"))
      (node (ref "R17") (pin "2") (pinfunction "2_2") (pintype "passive"))
    )
    (net (code "65") (name "Net-(IC3C--IN)") (class "Default")
      (node (ref "IC3") (pin "8") (pinfunction "OUT_8") (pintype "output"))
      (node (ref "IC3") (pin "9") (pinfunction "-IN_9") (pintype "input"))
    )
    (net (code "66") (name "Net-(IC3D-+IN)") (class "Default")
      (node (ref "IC3") (pin "12") (pinfunction "+IN_12") (pintype "input"))
      (node (ref "R20") (pin "1") (pinfunction "1_1") (pintype "passive"))
      (node (ref "R21") (pin "2") (pinfunction "2_2") (pintype "passive"))
    )
    (net (code "67") (name "Net-(IC4A-DET)") (class "Default")
      (node (ref "C61") (pin "-") (pinfunction "-_-") (pintype "passive"))
      (node (ref "IC4") (pin "3") (pinfunction "DET_3") (pintype "passive"))
    )
    (net (code "68") (name "Net-(IC4A-G1)") (class "Default")
      (node (ref "IC4") (pin "1") (pinfunction "G1_1") (pintype "passive"))
      (node (ref "R25") (pin "1") (pinfunction "1_1") (pintype "passive"))
      (node (ref "R26") (pin "2") (pinfunction "2_2") (pintype "passive"))
    )
    (net (code "69") (name "Net-(IC4A-G2)") (class "Default")
      (node (ref "IC4") (pin "2") (pinfunction "G2_2") (pintype "passive"))
      (node (ref "R25") (pin "2") (pinfunction "2_2") (pintype "passive"))
    )
    (net (code "70") (name "Net-(IC4A-INT)") (class "Default")
      (node (ref "C59") (pin "+") (pinfunction "+_+") (pintype "passive"))
      (node (ref "IC4") (pin "12") (pinfunction "INT_12") (pintype "passive"))
    )
    (net (code "71") (name "Net-(IC4A-OUT)") (class "Default")
      (node (ref "C61") (pin "+") (pinfunction "+_+") (pintype "passive"))
      (node (ref "IC4") (pin "4") (pinfunction "OUT_4") (pintype "output"))
      (node (ref "IC4") (pin "5") (pinfunction "BUFIN_5") (pintype "input"))
    )
    (net (code "72") (name "Net-(IC4A-SENSE)") (class "Default")
      (node (ref "IC4") (pin "11") (pinfunction "SENSE_11") (pintype "passive"))
      (node (ref "R23") (pin "2") (pinfunction "2_2") (pintype "passive"))
    )
    (net (code "73") (name "Net-(IC4B-BUFG)") (class "Default")
      (node (ref "C60") (pin "+") (pinfunction "+_+") (pintype "passive"))
      (node (ref "IC4") (pin "6") (pinfunction "BUFG_6") (pintype "input"))
      (node (ref "IC4") (pin "7") (pinfunction "BUFO_7") (pintype "output"))
    )
    (net (code "74") (name "Net-(IC4B-VREF)") (class "Default")
      (node (ref "C62") (pin "+") (pinfunction "+_+") (pintype "passive"))
      (node (ref "IC4") (pin "10") (pinfunction "VREF_10") (pintype "passive"))
    )
    (net (code "75") (name "Net-(IC5-COM)") (class "Default")
      (node (ref "IC5") (pin "5") (pinfunction "COM_5") (pintype "passive"))
      (node (ref "R10") (pin "1") (pinfunction "1_1") (pintype "passive"))
    )
    (net (code "76") (name "Net-(IC5-NO)") (class "Default")
      (node (ref "IC5") (pin "6") (pinfunction "NO_6") (pintype "passive"))
      (node (ref "R5") (pin "1") (pinfunction "1_1") (pintype "passive"))
      (node (ref "R6") (pin "2") (pinfunction "2_2") (pintype "passive"))
    )
    (net (code "77") (name "Net-(IC6C-SCL)") (class "Default")
      (node (ref "IC6") (pin "14") (pinfunction "SCL_14") (pintype "input"))
      (node (ref "R7") (pin "2") (pinfunction "2_2") (pintype "passive"))
    )
    (net (code "78") (name "Net-(IC6C-SDA)") (class "Default")
      (node (ref "IC6") (pin "13") (pinfunction "SDA_13") (pintype "bidirectional"))
      (node (ref "R8") (pin "2") (pinfunction "2_2") (pintype "passive"))
    )
    (net (code "79") (name "Net-(IC7-+IN)") (class "Default")
      (node (ref "C20") (pin "+") (pinfunction "+_+") (pintype "passive"))
      (node (ref "D1") (pin "A") (pinfunction "A_A") (pintype "passive"))
      (node (ref "IC7") (pin "3") (pinfunction "+IN_3") (pintype "input"))
      (node (ref "IC8") (pin "10") (pinfunction "+IN_10") (pintype "input"))
      (node (ref "IC8") (pin "12") (pinfunction "+IN_12") (pintype "input"))
      (node (ref "R29") (pin "1") (pinfunction "1_1") (pintype "passive"))
      (node (ref "R30") (pin "2") (pinfunction "2_2") (pintype "passive"))
    )
    (net (code "80") (name "Net-(IC7--IN)") (class "Default")
      (node (ref "C22") (pin "2") (pinfunction "2_2") (pintype "passive"))
      (node (ref "IC7") (pin "2") (pinfunction "-IN_2") (pintype "input"))
      (node (ref "R32") (pin "2") (pinfunction "2_2") (pintype "passive"))
      (node (ref "R36") (pin "1") (pinfunction "1_1") (pintype "passive"))
    )
    (net (code "81") (name "Net-(IC7-CMP)") (class "Default")
      (node (ref "C24") (pin "2") (pinfunction "2_2") (pintype "passive"))
      (node (ref "IC7") (pin "5") (pinfunction "CMP_5") (pintype "passive"))
    )
    (net (code "82") (name "Net-(IC7-ON{slash}CMP)") (class "Default")
      (node (ref "C24") (pin "1") (pinfunction "1_1") (pintype "passive"))
      (node (ref "IC7") (pin "8") (pinfunction "ON/CMP_8") (pintype "passive"))
    )
    (net (code "83") (name "Net-(IC7-OUT)") (class "Default")
      (node (ref "C22") (pin "1") (pinfunction "1_1") (pintype "passive"))
      (node (ref "C25") (pin "1") (pinfunction "1_1") (pintype "passive"))
      (node (ref "C26") (pin "1") (pinfunction "1_1") (pintype "passive"))
      (node (ref "IC7") (pin "6") (pinfunction "OUT_6") (pintype "output"))
      (node (ref "R36") (pin "2") (pinfunction "2_2") (pintype "passive"))
    )
    (net (code "84") (name "Net-(IC8A-+IN)") (class "Default")
      (node (ref "C32") (pin "1") (pinfunction "1_1") (pintype "passive"))
      (node (ref "IC8") (pin "3") (pinfunction "+IN_3") (pintype "input"))
      (node (ref "R45") (pin "2") (pinfunction "2_2") (pintype "passive"))
      (node (ref "R47") (pin "2") (pinfunction "2_2") (pintype "passive"))
    )
    (net (code "85") (name "Net-(IC8A--IN)") (class "Default")
      (node (ref "C57") (pin "2") (pinfunction "2_2") (pintype "passive"))
      (node (ref "IC8") (pin "2") (pinfunction "-IN_2") (pintype "input"))
      (node (ref "R44") (pin "1") (pinfunction "1_1") (pintype "passive"))
      (node (ref "R48") (pin "2") (pinfunction "2_2") (pintype "passive"))
    )
    (net (code "86") (name "Net-(IC8A-OUT)") (class "Default")
      (node (ref "IC8") (pin "1") (pinfunction "OUT_1") (pintype "output"))
      (node (ref "R48") (pin "1") (pinfunction "1_1") (pintype "passive"))
      (node (ref "R51") (pin "1") (pinfunction "1_1") (pintype "passive"))
    )
    (net (code "87") (name "Net-(IC8B-+IN)") (class "Default")
      (node (ref "C23") (pin "+") (pinfunction "+_+") (pintype "passive"))
      (node (ref "IC8") (pin "5") (pinfunction "+IN_5") (pintype "input"))
      (node (ref "R37") (pin "2") (pinfunction "2_2") (pintype "passive"))
    )
    (net (code "88") (name "Net-(IC8B--IN)") (class "Default")
      (node (ref "IC8") (pin "6") (pinfunction "-IN_6") (pintype "input"))
      (node (ref "R38") (pin "2") (pinfunction "2_2") (pintype "passive"))
      (node (ref "R39") (pin "1") (pinfunction "1_1") (pintype "passive"))
    )
    (net (code "89") (name "Net-(IC8B-OUT)") (class "Default")
      (node (ref "IC8") (pin "7") (pinfunction "OUT_7") (pintype "output"))
      (node (ref "R39") (pin "2") (pinfunction "2_2") (pintype "passive"))
      (node (ref "R41") (pin "1") (pinfunction "1_1") (pintype "passive"))
    )
    (net (code "90") (name "Net-(IC8C--IN)") (class "Default")
      (node (ref "IC8") (pin "8") (pinfunction "OUT_8") (pintype "output"))
      (node (ref "IC8") (pin "9") (pinfunction "-IN_9") (pintype "input"))
    )
    (net (code "91") (name "Net-(IC9-INT)") (class "Default")
      (node (ref "C36") (pin "+") (pinfunction "+_+") (pintype "passive"))
      (node (ref "IC9") (pin "4") (pinfunction "INT_4") (pintype "bidirectional"))
    )
    (net (code "92") (name "Net-(IC9-SENSE)") (class "Default")
      (node (ref "IC9") (pin "6") (pinfunction "SENSE_6") (pintype "bidirectional"))
      (node (ref "R56") (pin "2") (pinfunction "2_2") (pintype "passive"))
    )
    (net (code "93") (name "Net-(IC9-VREF)") (class "Default")
      (node (ref "C37") (pin "+") (pinfunction "+_+") (pintype "passive"))
      (node (ref "IC9") (pin "5") (pinfunction "VREF_5") (pintype "bidirectional"))
    )
    (net (code "94") (name "Net-(IC10-NO)") (class "Default")
      (node (ref "IC10") (pin "6") (pinfunction "NO_6") (pintype "passive"))
      (node (ref "R57") (pin "2") (pinfunction "2_2") (pintype "passive"))
    )
    (net (code "95") (name "Net-(IC11-NO)") (class "Default")
      (node (ref "C41") (pin "1") (pinfunction "1_1") (pintype "passive"))
      (node (ref "IC11") (pin "6") (pinfunction "NO_6") (pintype "passive"))
    )
    (net (code "96") (name "Net-(IC12A-A)") (class "Default")
      (node (ref "IC12") (pin "1") (pinfunction "A_1") (pintype "passive"))
      (node (ref "IC17") (pin "6") (pinfunction "-IN_6") (pintype "input"))
      (node (ref "IC17") (pin "7") (pinfunction "OUT_7") (pintype "output"))
    )
    (net (code "97") (name "Net-(IC12A-S)") (class "Default")
      (node (ref "IC12") (pin "7") (pinfunction "S_7") (pintype "passive"))
      (node (ref "IC17") (pin "3") (pinfunction "+IN_3") (pintype "input"))
    )
    (net (code "98") (name "Net-(IC13A-+IN)") (class "Default")
      (node (ref "IC13") (pin "12") (pinfunction "+IN_12") (pintype "input"))
      (node (ref "IC13") (pin "3") (pinfunction "+IN_3") (pintype "input"))
      (node (ref "R74") (pin "2") (pinfunction "2_2") (pintype "passive"))
      (node (ref "R77") (pin "1") (pinfunction "1_1") (pintype "passive"))
    )
    (net (code "99") (name "Net-(IC13A--IN)") (class "Default")
      (node (ref "IC13") (pin "1") (pinfunction "OUT_1") (pintype "output"))
      (node (ref "IC13") (pin "2") (pinfunction "-IN_2") (pintype "input"))
      (node (ref "IC6") (pin "7") (pinfunction "L_7") (pintype "passive"))
      (node (ref "IC6") (pin "9") (pinfunction "L_9") (pintype "passive"))
    )
    (net (code "100") (name "Net-(IC13B-+IN)") (class "Default")
      (node (ref "IC13") (pin "5") (pinfunction "+IN_5") (pintype "input"))
      (node (ref "IC6") (pin "6") (pinfunction "W_6") (pintype "passive"))
    )
    (net (code "101") (name "Net-(IC13C-+IN)") (class "Default")
      (node (ref "IC13") (pin "10") (pinfunction "+IN_10") (pintype "input"))
      (node (ref "IC6") (pin "11") (pinfunction "W_11") (pintype "passive"))
    )
    (net (code "102") (name "Net-(IC15-NC)") (class "Default")
      (node (ref "C60") (pin "-") (pinfunction "-_-") (pintype "passive"))
      (node (ref "IC15") (pin "4") (pinfunction "NC_4") (pintype "passive"))
      (node (ref "R27") (pin "1") (pinfunction "1_1") (pintype "passive"))
    )
    (net (code "103") (name "Net-(IC15-NO)") (class "Default")
      (node (ref "IC15") (pin "6") (pinfunction "NO_6") (pintype "passive"))
      (node (ref "R27") (pin "2") (pinfunction "2_2") (pintype "passive"))
      (node (ref "R35") (pin "1") (pinfunction "1_1") (pintype "passive"))
    )
    (net (code "104") (name "Net-(IC16-BYPASS)") (class "Default")
      (node (ref "C50") (pin "+") (pinfunction "+_+") (pintype "passive"))
      (node (ref "IC16") (pin "3") (pinfunction "BYPASS_3") (pintype "bidirectional"))
    )
    (net (code "105") (name "Net-(IC16-INA)") (class "Default")
      (node (ref "IC16") (pin "2") (pinfunction "INA_2") (pintype "bidirectional"))
      (node (ref "R75") (pin "2") (pinfunction "2_2") (pintype "passive"))
      (node (ref "R78") (pin "1") (pinfunction "1_1") (pintype "passive"))
    )
    (net (code "106") (name "Net-(IC16-INB)") (class "Default")
      (node (ref "IC16") (pin "6") (pinfunction "INB_6") (pintype "bidirectional"))
      (node (ref "R76") (pin "2") (pinfunction "2_2") (pintype "passive"))
      (node (ref "R79") (pin "1") (pinfunction "1_1") (pintype "passive"))
    )
    (net (code "107") (name "Net-(IC16-OUTA)") (class "Default")
      (node (ref "C54") (pin "+") (pinfunction "+_+") (pintype "passive"))
      (node (ref "IC16") (pin "1") (pinfunction "OUTA_1") (pintype "output"))
      (node (ref "R78") (pin "2") (pinfunction "2_2") (pintype "passive"))
    )
    (net (code "108") (name "Net-(IC16-OUTB)") (class "Default")
      (node (ref "C55") (pin "+") (pinfunction "+_+") (pintype "passive"))
      (node (ref "IC16") (pin "7") (pinfunction "OUTB_7") (pintype "output"))
      (node (ref "R79") (pin "2") (pinfunction "2_2") (pintype "passive"))
    )
    (net (code "109") (name "Net-(IC16-V+)") (class "Default")
      (node (ref "C51") (pin "1") (pinfunction "1_1") (pintype "passive"))
      (node (ref "C53") (pin "+") (pinfunction "+_+") (pintype "passive"))
      (node (ref "IC16") (pin "8") (pinfunction "V+_8") (pintype "power_in"))
      (node (ref "L2") (pin "2") (pinfunction "2_2") (pintype "passive"))
    )
    (net (code "110") (name "Net-(IC101-FB)") (class "Default")
      (node (ref "C103") (pin "2") (pinfunction "2_2") (pintype "passive"))
      (node (ref "IC101") (pin "3") (pinfunction "FB_3") (pintype "bidirectional"))
      (node (ref "R102") (pin "2") (pinfunction "2_2") (pintype "passive"))
      (node (ref "R103") (pin "1") (pinfunction "1_1") (pintype "passive"))
    )
    (net (code "111") (name "Net-(IC101-SW)") (class "Default")
      (node (ref "D101") (pin "A") (pinfunction "A_A") (pintype "bidirectional"))
      (node (ref "IC101") (pin "1") (pinfunction "SW_1") (pintype "bidirectional"))
      (node (ref "L101") (pin "P$2") (pinfunction "P$2_P$2") (pintype "passive"))
    )
    (net (code "112") (name "Net-(IC3001-CB)") (class "Default")
      (node (ref "C3007") (pin "1") (pinfunction "1_1") (pintype "passive"))
      (node (ref "IC3001") (pin "1") (pinfunction "CB_1") (pintype "bidirectional"))
    )
    (net (code "113") (name "Net-(IC3001-OUT)") (class "Default")
      (node (ref "C3007") (pin "2") (pinfunction "2_2") (pintype "passive"))
      (node (ref "D4") (pin "C") (pinfunction "C_C") (pintype "passive"))
      (node (ref "IC3001") (pin "8") (pinfunction "OUT_8") (pintype "bidirectional"))
      (node (ref "L3001") (pin "P$1") (pinfunction "P$1_P$1") (pintype "passive"))
    )
    (net (code "114") (name "Net-(T2-B)") (class "Default")
      (node (ref "R46") (pin "2") (pinfunction "2_2") (pintype "passive"))
      (node (ref "T2") (pin "1") (pinfunction "B_1") (pintype "passive"))
    )
    (net (code "115") (name "Net-(T2-C)") (class "Default")
      (node (ref "R49") (pin "1") (pinfunction "1_1") (pintype "passive"))
      (node (ref "T2") (pin "3") (pinfunction "C_3") (pintype "passive"))
    )
    (net (code "116") (name "Net-(T3-B)") (class "Default")
      (node (ref "C34") (pin "2") (pinfunction "2_2") (pintype "passive"))
      (node (ref "R50") (pin "2") (pinfunction "2_2") (pintype "passive"))
      (node (ref "R53") (pin "1") (pinfunction "1_1") (pintype "passive"))
      (node (ref "T3") (pin "1") (pinfunction "B_1") (pintype "passive"))
    )
    (net (code "117") (name "Net-(T3-E)") (class "Default")
      (node (ref "R54") (pin "1") (pinfunction "1_1") (pintype "passive"))
      (node (ref "T3") (pin "2") (pinfunction "E_2") (pintype "passive"))
    )
    (net (code "118") (name "Net-(T4-B)") (class "Default")
      (node (ref "C4") (pin "1") (pinfunction "1_1") (pintype "passive"))
      (node (ref "R1") (pin "2") (pinfunction "2_2") (pintype "passive"))
      (node (ref "R4") (pin "1") (pinfunction "1_1") (pintype "passive"))
      (node (ref "T4") (pin "1") (pinfunction "B_1") (pintype "passive"))
    )
    (net (code "119") (name "Net-(T4-C)") (class "Default")
      (node (ref "C12") (pin "1") (pinfunction "1_1") (pintype "passive"))
      (node (ref "R22") (pin "1") (pinfunction "1_1") (pintype "passive"))
      (node (ref "T4") (pin "3") (pinfunction "C_3") (pintype "passive"))
    )
    (net (code "120") (name "Net-(T5-D)") (class "Default")
      (node (ref "R70") (pin "2") (pinfunction "2_2") (pintype "passive"))
      (node (ref "T5") (pin "3") (pinfunction "D_3") (pintype "passive"))
    )
    (net (code "121") (name "RX_AUDIO") (class "Default")
      (node (ref "C35") (pin "-") (pinfunction "-_-") (pintype "passive"))
      (node (ref "JP1") (pin "12") (pinfunction "12_12") (pintype "passive"))
      (node (ref "R55") (pin "2") (pinfunction "2_2") (pintype "passive"))
    )
    (net (code "122") (name "RX_AUD_FLT") (class "Default")
      (node (ref "IC9") (pin "3") (pinfunction "INA_3") (pintype "passive"))
      (node (ref "IC9") (pin "8") (pinfunction "INB_8") (pintype "passive"))
      (node (ref "JP1") (pin "11") (pinfunction "11_11") (pintype "passive"))
      (node (ref "R19") (pin "1") (pinfunction "1_1") (pintype "passive"))
      (node (ref "R55") (pin "1") (pinfunction "1_1") (pintype "passive"))
    )
    (net (code "123") (name "RX_AUD_LIM") (class "Default")
      (node (ref "IC9") (pin "9") (pinfunction "OUTB_9") (pintype "output"))
      (node (ref "JP1") (pin "14") (pinfunction "14_14") (pintype "passive"))
      (node (ref "R19") (pin "2") (pinfunction "2_2") (pintype "passive"))
      (node (ref "R58") (pin "1") (pinfunction "1_1") (pintype "passive"))
    )
    (net (code "124") (name "RX_AUD_RET") (class "Default")
      (node (ref "IC11") (pin "5") (pinfunction "COM_5") (pintype "passive"))
      (node (ref "JP1") (pin "13") (pinfunction "13_13") (pintype "passive"))
      (node (ref "R58") (pin "2") (pinfunction "2_2") (pintype "passive"))
    )
    (net (code "125") (name "SCL") (class "Default")
      (node (ref "CN1") (pin "5") (pinfunction "5_5") (pintype "bidirectional"))
      (node (ref "IC1") (pin "19") (pinfunction "PC0(SCL)_19") (pintype "bidirectional"))
      (node (ref "IC12") (pin "5") (pinfunction "SCL_5") (pintype "input"))
      (node (ref "JP1") (pin "8") (pinfunction "8_8") (pintype "passive"))
      (node (ref "R7") (pin "1") (pinfunction "1_1") (pintype "passive"))
      (node (ref "R72") (pin "1") (pinfunction "1_1") (pintype "passive"))
    )
    (net (code "126") (name "SDA") (class "Default")
      (node (ref "CN1") (pin "6") (pinfunction "6_6") (pintype "bidirectional"))
      (node (ref "IC1") (pin "20") (pinfunction "PC1(SDA)_20") (pintype "bidirectional"))
      (node (ref "IC12") (pin "4") (pinfunction "SDA_4") (pintype "bidirectional"))
      (node (ref "JP1") (pin "5") (pinfunction "5_5") (pintype "passive"))
      (node (ref "R73") (pin "1") (pinfunction "1_1") (pintype "passive"))
      (node (ref "R8") (pin "1") (pinfunction "1_1") (pintype "passive"))
    )
    (net (code "127") (name "ST_IN") (class "Default")
      (node (ref "C23") (pin "-") (pinfunction "-_-") (pintype "passive"))
      (node (ref "IC17") (pin "1") (pinfunction "OUT_1") (pintype "output"))
      (node (ref "IC17") (pin "2") (pinfunction "-IN_2") (pintype "input"))
    )
    (net (code "128") (name "TC_IN") (class "Default")
      (node (ref "IC1") (pin "15") (pinfunction "(ICP)PD6_15") (pintype "bidirectional"))
      (node (ref "JP1") (pin "4") (pinfunction "4_4") (pintype "passive"))
    )
    (net (code "129") (name "TXA") (class "Default")
      (node (ref "C26") (pin "2") (pinfunction "2_2") (pintype "passive"))
      (node (ref "R16") (pin "2") (pinfunction "2_2") (pintype "passive"))
      (node (ref "R40") (pin "1") (pinfunction "1_1") (pintype "passive"))
      (node (ref "T3") (pin "3") (pinfunction "C_3") (pintype "passive"))
      (node (ref "TP1") (pin "TP") (pinfunction "TP_TP") (pintype "input"))
    )
    (net (code "130") (name "TX_AUDIO") (class "Default")
      (node (ref "C17") (pin "-") (pinfunction "-_-") (pintype "passive"))
      (node (ref "IC17") (pin "5") (pinfunction "+IN_5") (pintype "input"))
      (node (ref "JP1") (pin "15") (pinfunction "15_15") (pintype "passive"))
      (node (ref "R43") (pin "2") (pinfunction "2_2") (pintype "passive"))
    )
    (net (code "131") (name "TX_INT") (class "Default")
      (node (ref "IC10") (pin "5") (pinfunction "COM_5") (pintype "passive"))
      (node (ref "JP1") (pin "18") (pinfunction "18_18") (pintype "passive"))
      (node (ref "R43") (pin "1") (pinfunction "1_1") (pintype "passive"))
    )
    (net (code "132") (name "V+") (class "Default")
      (node (ref "C21") (pin "1") (pinfunction "1_1") (pintype "passive"))
      (node (ref "C27") (pin "1") (pinfunction "1_1") (pintype "passive"))
      (node (ref "C31") (pin "1") (pinfunction "1_1") (pintype "passive"))
      (node (ref "C34") (pin "1") (pinfunction "1_1") (pintype "passive"))
      (node (ref "D1") (pin "K") (pinfunction "C_K") (pintype "passive"))
      (node (ref "D9") (pin "A") (pinfunction "A_A") (pintype "passive"))
      (node (ref "IC7") (pin "7") (pinfunction "V+_7") (pintype "power_in"))
      (node (ref "IC8") (pin "4") (pinfunction "V+_4") (pintype "power_in"))
      (node (ref "L3") (pin "1") (pinfunction "1_1") (pintype "passive"))
      (node (ref "R29") (pin "2") (pinfunction "2_2") (pintype "passive"))
      (node (ref "R53") (pin "2") (pinfunction "2_2") (pintype "passive"))
      (node (ref "R54") (pin "2") (pinfunction "2_2") (pintype "passive"))
    )
    (net (code "133") (name "VBUS_SENSE") (class "Default")
      (node (ref "C10") (pin "1") (pinfunction "1_1") (pintype "passive"))
      (node (ref "IC1") (pin "35") (pinfunction "(ADC2)PA2_35") (pintype "bidirectional"))
      (node (ref "R12") (pin "1") (pinfunction "1_1") (pintype "passive"))
      (node (ref "R13") (pin "2") (pinfunction "2_2") (pintype "passive"))
    )
    (net (code "134") (name "VCC") (class "Default")
      (node (ref "C101") (pin "+") (pinfunction "+_+") (pintype "passive"))
      (node (ref "C102") (pin "1") (pinfunction "1_1") (pintype "passive"))
      (node (ref "C11") (pin "1") (pinfunction "1_1") (pintype "passive"))
      (node (ref "C3") (pin "1") (pinfunction "1_1") (pintype "passive"))
      (node (ref "C38") (pin "1") (pinfunction "1_1") (pintype "passive"))
      (node (ref "C43") (pin "1") (pinfunction "1_1") (pintype "passive"))
      (node (ref "C44") (pin "+") (pinfunction "+_+") (pintype "passive"))
      (node (ref "C5") (pin "1") (pinfunction "1_1") (pintype "passive"))
      (node (ref "C52") (pin "1") (pinfunction "1_1") (pintype "passive"))
      (node (ref "C63") (pin "2") (pinfunction "2_2") (pintype "passive"))
      (node (ref "C67") (pin "1") (pinfunction "1_1") (pintype "passive"))
      (node (ref "C68") (pin "1") (pinfunction "1_1") (pintype "passive"))
      (node (ref "C7") (pin "1") (pinfunction "1_1") (pintype "passive"))
      (node (ref "C8") (pin "1") (pinfunction "1_1") (pintype "passive"))
      (node (ref "C9") (pin "1") (pinfunction "1_1") (pintype "passive"))
      (node (ref "CN1") (pin "12") (pinfunction "12_12") (pintype "bidirectional"))
      (node (ref "CN1") (pin "15") (pinfunction "15_15") (pintype "bidirectional"))
      (node (ref "D3") (pin "A") (pinfunction "A_A") (pintype "passive"))
      (node (ref "IC1") (pin "17") (pinfunction "VCC1_17") (pintype "power_in"))
      (node (ref "IC1") (pin "27") (pinfunction "AVCC_27") (pintype "power_in"))
      (node (ref "IC1") (pin "38") (pinfunction "VCC2_38") (pintype "power_in"))
      (node (ref "IC1") (pin "5") (pinfunction "VCC_5") (pintype "power_in"))
      (node (ref "IC10") (pin "2") (pinfunction "VCC_2") (pintype "power_in"))
      (node (ref "IC101") (pin "4") (pinfunction "~{SHDN}_4") (pintype "bidirectional"))
      (node (ref "IC101") (pin "5") (pinfunction "VIN_5") (pintype "power_in"))
      (node (ref "IC12") (pin "6") (pinfunction "VCC_6") (pintype "power_in"))
      (node (ref "IC15") (pin "2") (pinfunction "VCC_2") (pintype "power_in"))
      (node (ref "IC17") (pin "8") (pinfunction "V+_8") (pintype "power_in"))
      (node (ref "IC3") (pin "4") (pinfunction "V+_4") (pintype "power_in"))
      (node (ref "IC3001") (pin "4") (pinfunction "FB_4") (pintype "bidirectional"))
      (node (ref "IC5") (pin "2") (pinfunction "VCC_2") (pintype "power_in"))
      (node (ref "JP1") (pin "16") (pinfunction "16_16") (pintype "passive"))
      (node (ref "JP1") (pin "9") (pinfunction "9_9") (pintype "passive"))
      (node (ref "L101") (pin "P$1") (pinfunction "P$1_P$1") (pintype "passive"))
      (node (ref "L2") (pin "1") (pinfunction "1_1") (pintype "passive"))
      (node (ref "L3001") (pin "P$2") (pinfunction "P$2_P$2") (pintype "passive"))
      (node (ref "L4") (pin "2") (pinfunction "2_2") (pintype "passive"))
      (node (ref "R14") (pin "2") (pinfunction "2_2") (pintype "passive"))
      (node (ref "R20") (pin "2") (pinfunction "2_2") (pintype "passive"))
      (node (ref "R22") (pin "2") (pinfunction "2_2") (pintype "passive"))
      (node (ref "R24") (pin "1") (pinfunction "1_1") (pintype "passive"))
      (node (ref "R3") (pin "1") (pinfunction "1_1") (pintype "passive"))
      (node (ref "R71") (pin "2") (pinfunction "2_2") (pintype "passive"))
      (node (ref "R72") (pin "2") (pinfunction "2_2") (pintype "passive"))
      (node (ref "R73") (pin "2") (pinfunction "2_2") (pintype "passive"))
      (node (ref "SV1") (pin "2") (pinfunction "2_2") (pintype "passive"))
      (node (ref "T5") (pin "2") (pinfunction "S_2") (pintype "passive"))
    )
    (net (code "135") (name "V_BUS") (class "Default")
      (node (ref "D2") (pin "A") (pinfunction "A_A") (pintype "passive"))
      (node (ref "X2") (pin "2") (pinfunction "2_2") (pintype "passive"))
    )
    (net (code "136") (name "V_I+") (class "Default")
      (node (ref "C45") (pin "+") (pinfunction "+_+") (pintype "passive"))
      (node (ref "C46") (pin "1") (pinfunction "1_1") (pintype "passive"))
      (node (ref "D3") (pin "C") (pinfunction "C_C") (pintype "passive"))
      (node (ref "D9") (pin "C") (pinfunction "C_C") (pintype "passive"))
      (node (ref "IC3001") (pin "7") (pinfunction "IN_7") (pintype "bidirectional"))
      (node (ref "R12") (pin "2") (pinfunction "2_2") (pintype "passive"))
    )
    (net (code "137") (name "unconnected-(CN1-Pad13)") (class "Default")
      (node (ref "CN1") (pin "13") (pinfunction "13_13") (pintype "bidirectional"))
    )
    (net (code "138") (name "unconnected-(IC1-(ADC1)PA1-Pad36)") (class "Default")
      (node (ref "IC1") (pin "36") (pinfunction "(ADC1)PA1_36") (pintype "bidirectional"))
    )
    (net (code "139") (name "unconnected-(IC1-(ADC4)PA4-Pad33)") (class "Default")
      (node (ref "IC1") (pin "33") (pinfunction "(ADC4)PA4_33") (pintype "bidirectional"))
    )
    (net (code "140") (name "unconnected-(IC1-(ADC5)PA5-Pad32)") (class "Default")
      (node (ref "IC1") (pin "32") (pinfunction "(ADC5)PA5_32") (pintype "bidirectional"))
    )
    (net (code "141") (name "unconnected-(IC1-(ADC6)PA6-Pad31)") (class "Default")
      (node (ref "IC1") (pin "31") (pinfunction "(ADC6)PA6_31") (pintype "bidirectional"))
    )
    (net (code "142") (name "unconnected-(IC1-(ADC7)PA7-Pad30)") (class "Default")
      (node (ref "IC1") (pin "30") (pinfunction "(ADC7)PA7_30") (pintype "bidirectional"))
    )
    (net (code "143") (name "unconnected-(IC1-(OC2)PD7-Pad16)") (class "Default")
      (node (ref "IC1") (pin "16") (pinfunction "(OC2)PD7_16") (pintype "bidirectional"))
    )
    (net (code "144") (name "unconnected-(IC1-(TCK)PC2-Pad21)") (class "Default")
      (node (ref "IC1") (pin "21") (pinfunction "(TCK)PC2_21") (pintype "bidirectional"))
    )
    (net (code "145") (name "unconnected-(IC1-(TDO)PC4-Pad23)") (class "Default")
      (node (ref "IC1") (pin "23") (pinfunction "(TDO)PC4_23") (pintype "bidirectional"))
    )
    (net (code "146") (name "unconnected-(IC7-ON-Pad1)") (class "Default")
      (node (ref "IC7") (pin "1") (pinfunction "ON_1") (pintype "passive"))
    )
    (net (code "147") (name "unconnected-(IC9-OUTA-Pad2)") (class "Default")
      (node (ref "IC9") (pin "2") (pinfunction "OUTA_2") (pintype "output"))
    )
    (net (code "148") (name "unconnected-(IC11-NC-Pad4)") (class "Default")
      (node (ref "IC11") (pin "4") (pinfunction "NC_4") (pintype "passive"))
    )
    (net (code "149") (name "unconnected-(IC3001-EN-Pad5)") (class "Default")
      (node (ref "IC3001") (pin "5") (pinfunction "EN_5") (pintype "bidirectional"))
    )
    (net (code "150") (name "unconnected-(JP1-Pad6)") (class "Default")
      (node (ref "JP1") (pin "6") (pinfunction "6_6") (pintype "passive"))
    )
    (net (code "151") (name "~{AVR_CS0}") (class "Default")
      (node (ref "CN1") (pin "11") (pinfunction "11_11") (pintype "bidirectional"))
      (node (ref "IC1") (pin "44") (pinfunction "(SS)PB4_44") (pintype "bidirectional"))
    )
    (net (code "152") (name "~{AVR_RST}") (class "Default")
      (node (ref "CN1") (pin "14") (pinfunction "14_14") (pintype "bidirectional"))
      (node (ref "IC1") (pin "4") (pinfunction "RESET_4") (pintype "input"))
      (node (ref "R3") (pin "2") (pinfunction "2_2") (pintype "passive"))
      (node (ref "SV1") (pin "5") (pinfunction "5_5") (pintype "passive"))
    )
    (net (code "153") (name "~{CALL_IN}") (class "Default")
      (node (ref "IC1") (pin "40") (pinfunction "(T0/XCK)PB0_40") (pintype "bidirectional"))
      (node (ref "IC3") (pin "7") (pinfunction "OUT_7") (pintype "output"))
      (node (ref "R18") (pin "2") (pinfunction "2_2") (pintype "passive"))
    )
    (net (code "154") (name "~{DRST}") (class "Default")
      (node (ref "CN1") (pin "10") (pinfunction "10_10") (pintype "bidirectional"))
      (node (ref "IC1") (pin "34") (pinfunction "(ADC3)PA3_34") (pintype "bidirectional"))
    )
    (net (code "155") (name "~{MUTE_LINE}") (class "Default")
      (node (ref "IC1") (pin "42") (pinfunction "(AIN0/INT2)PB2_42") (pintype "bidirectional"))
      (node (ref "IC11") (pin "1") (pinfunction "CTL_1") (pintype "input"))
    )
    (net (code "156") (name "~{PHANTOM_ON}") (class "Default")
      (node (ref "IC1") (pin "22") (pinfunction "(TMS)PC3_22") (pintype "bidirectional"))
      (node (ref "R71") (pin "1") (pinfunction "1_1") (pintype "passive"))
      (node (ref "T5") (pin "1") (pinfunction "G_1") (pintype "passive"))
    )
    (net (code "157") (name "~{PON}") (class "Default")
      (node (ref "D7") (pin "A") (pinfunction "A_A") (pintype "bidirectional"))
      (node (ref "JP1") (pin "2") (pinfunction "2_2") (pintype "passive"))
    )
  )
)
